# Interface.net
KiCad netlist of a schematic drawn in Altium Designer
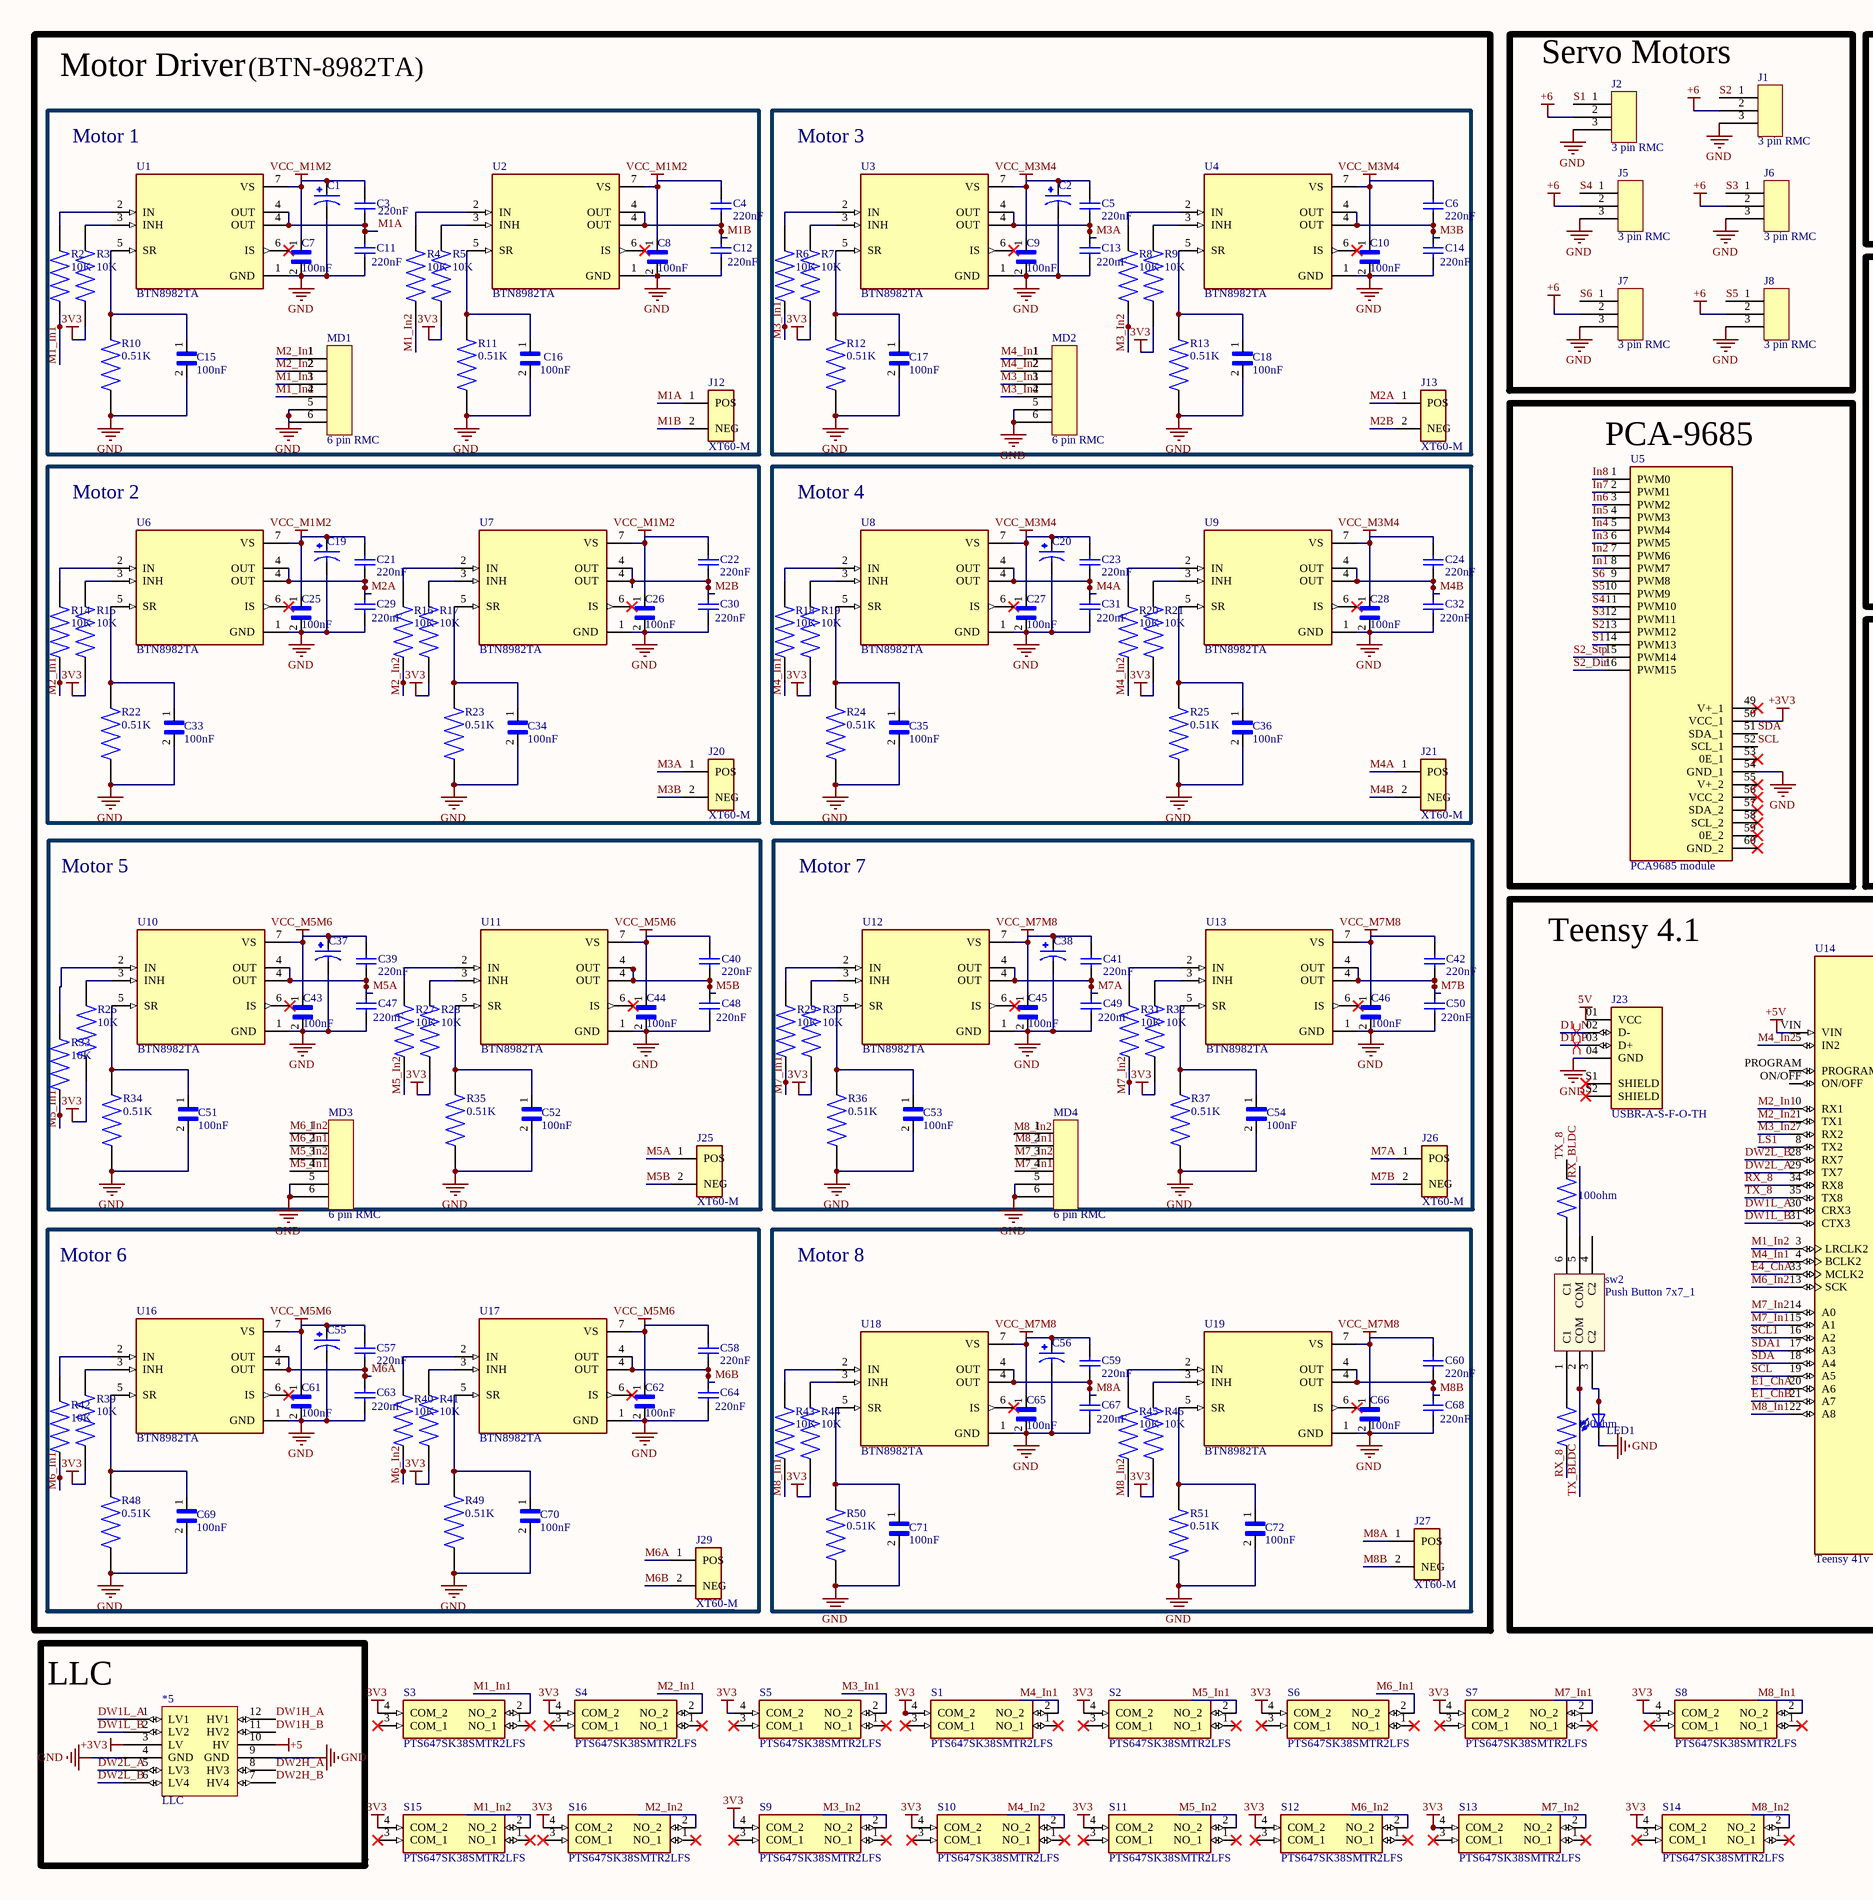
[diagram p0: Interface.SchDoc, left]
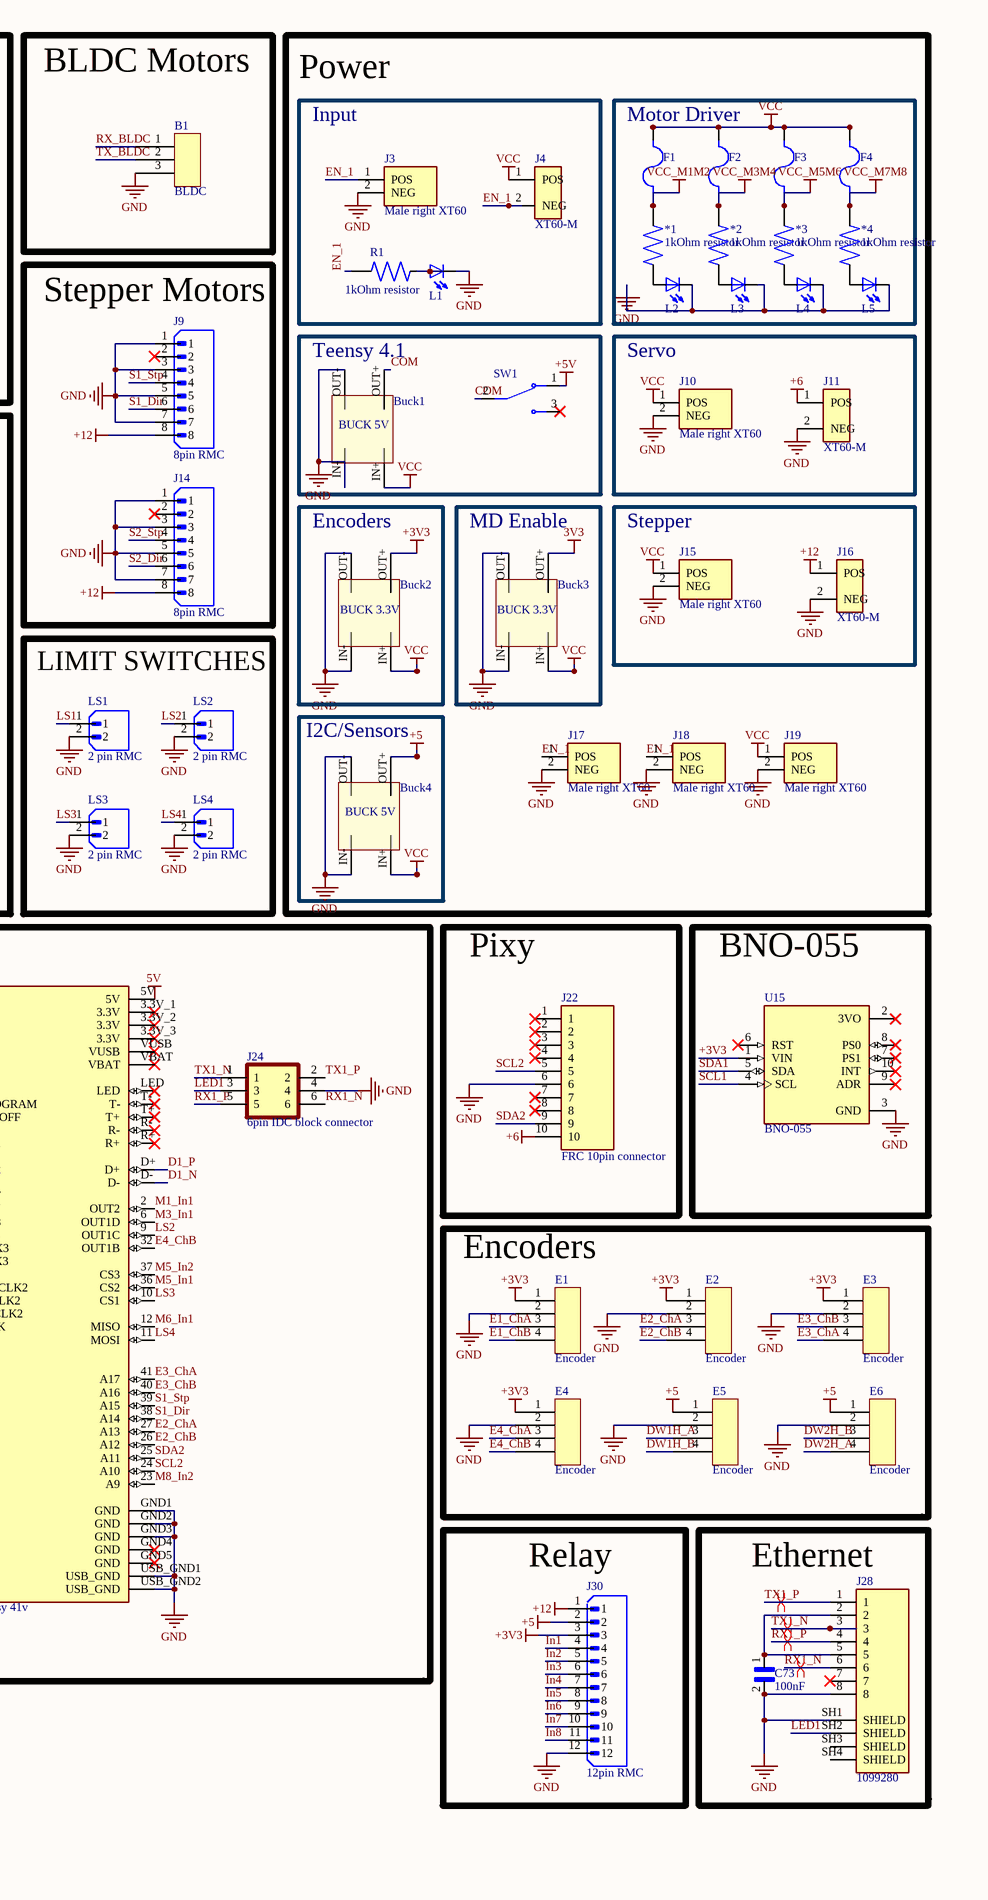
[diagram p1: Interface.SchDoc, right]

(export (version "E")
  (design (tool "Eeschema 10.0.6"))
  (components
    (comp (ref "*1")
      (value "1kOhm resistor")
      (footprint "1kOhm Resistor")
      (libsource (lib "BOT1_2025") (part "1kOhm resistor"))
    )
    (comp (ref "*2")
      (value "1kOhm resistor")
      (footprint "1kOhm Resistor")
      (libsource (lib "BOT1_2025") (part "1kOhm resistor"))
    )
    (comp (ref "*3")
      (value "1kOhm resistor")
      (footprint "1kOhm Resistor")
      (libsource (lib "BOT1_2025") (part "1kOhm resistor"))
    )
    (comp (ref "*4")
      (value "1kOhm resistor")
      (footprint "1kOhm Resistor")
      (libsource (lib "BOT1_2025") (part "1kOhm resistor"))
    )
    (comp (ref "*5") (value "LLC") (footprint "LLC") (libsource (lib "BOT1_2025") (part "LLC")))
    (comp (ref "B1")
      (value "BLDC")
      (footprint "Header JST 1X03")
      (libsource (lib "BOT1_2025") (part "3 pin RMC"))
    )
    (comp (ref "Buck1")
      (value "CN3900 5V")
      (footprint "CN3903 Dubai buck 5V")
      (libsource (lib "BOT1_2025") (part "CN3900 5V"))
    )
    (comp (ref "Buck2")
      (value "CN3900 3.3V")
      (footprint "CN3903 Dubai buck 3.3V")
      (libsource (lib "BOT1_2025") (part "CN3900 3.3V"))
    )
    (comp (ref "Buck3")
      (value "CN3900 3.3V")
      (footprint "CN3903 Dubai buck 3.3V")
      (libsource (lib "BOT1_2025") (part "CN3900 3.3V"))
    )
    (comp (ref "Buck4")
      (value "CN3900 5V")
      (footprint "CN3903 Dubai buck 5V")
      (libsource (lib "BOT1_2025") (part "CN3900 5V"))
    )
    (comp (ref "C1")
      (value "1000uF 25V Capacitor")
      (footprint "1000uF 25V Capacitor")
      (description "CAP ALUM 1000UF 20% 25V RADIAL")
      (fields (field (name "MP") "EEUTA1E102LB") (field (name "MF") "Panasonic"))
      (libsource (lib "BOT1_2025") (part "1000uF 25V Capacitor"))
    )
    (comp (ref "C2")
      (value "1000uF 25V Capacitor")
      (footprint "1000uF 25V Capacitor")
      (description "CAP ALUM 1000UF 20% 25V RADIAL")
      (fields (field (name "MP") "EEUTA1E102LB") (field (name "MF") "Panasonic"))
      (libsource (lib "BOT1_2025") (part "1000uF 25V Capacitor"))
    )
    (comp (ref "C3")
      (value "220nF")
      (footprint "WCAP-CSST_0805_L2W1.25H1.25")
      (fields
        (field (name "MANUFACTURER PART NUMBER") "885382207008")
        (field (name "MANUFACTURER") "Wurth Elektronik")
      )
      (libsource (lib "BOT1_2025") (part "885382207008"))
    )
    (comp (ref "C4")
      (value "220nF")
      (footprint "WCAP-CSST_0805_L2W1.25H1.25")
      (fields
        (field (name "MANUFACTURER PART NUMBER") "885382207008")
        (field (name "MANUFACTURER") "Wurth Elektronik")
      )
      (libsource (lib "BOT1_2025") (part "885382207008"))
    )
    (comp (ref "C5")
      (value "220nF")
      (footprint "WCAP-CSST_0805_L2W1.25H1.25")
      (fields
        (field (name "MANUFACTURER PART NUMBER") "885382207008")
        (field (name "MANUFACTURER") "Wurth Elektronik")
      )
      (libsource (lib "BOT1_2025") (part "885382207008"))
    )
    (comp (ref "C6")
      (value "220nF")
      (footprint "WCAP-CSST_0805_L2W1.25H1.25")
      (fields
        (field (name "MANUFACTURER PART NUMBER") "885382207008")
        (field (name "MANUFACTURER") "Wurth Elektronik")
      )
      (libsource (lib "BOT1_2025") (part "885382207008"))
    )
    (comp (ref "C7")
      (value "100nF")
      (footprint "BOT1_2025:CAPC2012X88N")
      (description "0.1ÂµF Â±10% 50V Ceramic Capacitor X7R 0805 _2012 Metric_")
      (fields (field (name "MF") "KEMET") (field (name "DIGI-KEY_PART_NUMBER") "399-5110-1-ND"))
      (libsource (lib "BOT1_2025") (part "C0805F104K5RACTU"))
    )
    (comp (ref "C8")
      (value "100nF")
      (footprint "BOT1_2025:CAPC2012X88N")
      (description "0.1ÂµF Â±10% 50V Ceramic Capacitor X7R 0805 _2012 Metric_")
      (fields (field (name "MF") "KEMET") (field (name "DIGI-KEY_PART_NUMBER") "399-5110-1-ND"))
      (libsource (lib "BOT1_2025") (part "C0805F104K5RACTU"))
    )
    (comp (ref "C9")
      (value "100nF")
      (footprint "BOT1_2025:CAPC2012X88N")
      (description "0.1ÂµF Â±10% 50V Ceramic Capacitor X7R 0805 _2012 Metric_")
      (fields (field (name "MF") "KEMET") (field (name "DIGI-KEY_PART_NUMBER") "399-5110-1-ND"))
      (libsource (lib "BOT1_2025") (part "C0805F104K5RACTU"))
    )
    (comp (ref "C10")
      (value "100nF")
      (footprint "BOT1_2025:CAPC2012X88N")
      (description "0.1ÂµF Â±10% 50V Ceramic Capacitor X7R 0805 _2012 Metric_")
      (fields (field (name "MF") "KEMET") (field (name "DIGI-KEY_PART_NUMBER") "399-5110-1-ND"))
      (libsource (lib "BOT1_2025") (part "C0805F104K5RACTU"))
    )
    (comp (ref "C11")
      (value "220nF")
      (footprint "WCAP-CSST_0805_L2W1.25H1.25")
      (fields
        (field (name "MANUFACTURER PART NUMBER") "885382207008")
        (field (name "MANUFACTURER") "Wurth Elektronik")
      )
      (libsource (lib "BOT1_2025") (part "885382207008"))
    )
    (comp (ref "C12")
      (value "220nF")
      (footprint "WCAP-CSST_0805_L2W1.25H1.25")
      (fields
        (field (name "MANUFACTURER PART NUMBER") "885382207008")
        (field (name "MANUFACTURER") "Wurth Elektronik")
      )
      (libsource (lib "BOT1_2025") (part "885382207008"))
    )
    (comp (ref "C13")
      (value "220nF")
      (footprint "WCAP-CSST_0805_L2W1.25H1.25")
      (fields
        (field (name "MANUFACTURER PART NUMBER") "885382207008")
        (field (name "MANUFACTURER") "Wurth Elektronik")
      )
      (libsource (lib "BOT1_2025") (part "885382207008"))
    )
    (comp (ref "C14")
      (value "220nF")
      (footprint "WCAP-CSST_0805_L2W1.25H1.25")
      (fields
        (field (name "MANUFACTURER PART NUMBER") "885382207008")
        (field (name "MANUFACTURER") "Wurth Elektronik")
      )
      (libsource (lib "BOT1_2025") (part "885382207008"))
    )
    (comp (ref "C15")
      (value "100nF")
      (footprint "BOT1_2025:CAPC2012X88N")
      (description "0.1ÂµF Â±10% 50V Ceramic Capacitor X7R 0805 _2012 Metric_")
      (fields (field (name "MF") "KEMET") (field (name "DIGI-KEY_PART_NUMBER") "399-5110-1-ND"))
      (libsource (lib "BOT1_2025") (part "C0805F104K5RACTU"))
    )
    (comp (ref "C16")
      (value "100nF")
      (footprint "BOT1_2025:CAPC2012X88N")
      (description "0.1ÂµF Â±10% 50V Ceramic Capacitor X7R 0805 _2012 Metric_")
      (fields (field (name "MF") "KEMET") (field (name "DIGI-KEY_PART_NUMBER") "399-5110-1-ND"))
      (libsource (lib "BOT1_2025") (part "C0805F104K5RACTU"))
    )
    (comp (ref "C17")
      (value "100nF")
      (footprint "BOT1_2025:CAPC2012X88N")
      (description "0.1ÂµF Â±10% 50V Ceramic Capacitor X7R 0805 _2012 Metric_")
      (fields (field (name "MF") "KEMET") (field (name "DIGI-KEY_PART_NUMBER") "399-5110-1-ND"))
      (libsource (lib "BOT1_2025") (part "C0805F104K5RACTU"))
    )
    (comp (ref "C18")
      (value "100nF")
      (footprint "BOT1_2025:CAPC2012X88N")
      (description "0.1ÂµF Â±10% 50V Ceramic Capacitor X7R 0805 _2012 Metric_")
      (fields (field (name "MF") "KEMET") (field (name "DIGI-KEY_PART_NUMBER") "399-5110-1-ND"))
      (libsource (lib "BOT1_2025") (part "C0805F104K5RACTU"))
    )
    (comp (ref "C19")
      (value "1000uF 25V Capacitor")
      (footprint "1000uF 25V Capacitor")
      (description "CAP ALUM 1000UF 20% 25V RADIAL")
      (fields (field (name "MP") "EEUTA1E102LB") (field (name "MF") "Panasonic"))
      (libsource (lib "BOT1_2025") (part "1000uF 25V Capacitor"))
    )
    (comp (ref "C20")
      (value "1000uF 25V Capacitor")
      (footprint "1000uF 25V Capacitor")
      (description "CAP ALUM 1000UF 20% 25V RADIAL")
      (fields (field (name "MP") "EEUTA1E102LB") (field (name "MF") "Panasonic"))
      (libsource (lib "BOT1_2025") (part "1000uF 25V Capacitor"))
    )
    (comp (ref "C21")
      (value "220nF")
      (footprint "WCAP-CSST_0805_L2W1.25H1.25")
      (fields
        (field (name "MANUFACTURER PART NUMBER") "885382207008")
        (field (name "MANUFACTURER") "Wurth Elektronik")
      )
      (libsource (lib "BOT1_2025") (part "885382207008"))
    )
    (comp (ref "C22")
      (value "220nF")
      (footprint "WCAP-CSST_0805_L2W1.25H1.25")
      (fields
        (field (name "MANUFACTURER PART NUMBER") "885382207008")
        (field (name "MANUFACTURER") "Wurth Elektronik")
      )
      (libsource (lib "BOT1_2025") (part "885382207008"))
    )
    (comp (ref "C23")
      (value "220nF")
      (footprint "WCAP-CSST_0805_L2W1.25H1.25")
      (fields
        (field (name "MANUFACTURER PART NUMBER") "885382207008")
        (field (name "MANUFACTURER") "Wurth Elektronik")
      )
      (libsource (lib "BOT1_2025") (part "885382207008"))
    )
    (comp (ref "C24")
      (value "220nF")
      (footprint "WCAP-CSST_0805_L2W1.25H1.25")
      (fields
        (field (name "MANUFACTURER PART NUMBER") "885382207008")
        (field (name "MANUFACTURER") "Wurth Elektronik")
      )
      (libsource (lib "BOT1_2025") (part "885382207008"))
    )
    (comp (ref "C25")
      (value "100nF")
      (footprint "BOT1_2025:CAPC2012X88N")
      (description "0.1ÂµF Â±10% 50V Ceramic Capacitor X7R 0805 _2012 Metric_")
      (fields (field (name "MF") "KEMET") (field (name "DIGI-KEY_PART_NUMBER") "399-5110-1-ND"))
      (libsource (lib "BOT1_2025") (part "C0805F104K5RACTU"))
    )
    (comp (ref "C26")
      (value "100nF")
      (footprint "BOT1_2025:CAPC2012X88N")
      (description "0.1ÂµF Â±10% 50V Ceramic Capacitor X7R 0805 _2012 Metric_")
      (fields (field (name "MF") "KEMET") (field (name "DIGI-KEY_PART_NUMBER") "399-5110-1-ND"))
      (libsource (lib "BOT1_2025") (part "C0805F104K5RACTU"))
    )
    (comp (ref "C27")
      (value "100nF")
      (footprint "BOT1_2025:CAPC2012X88N")
      (description "0.1ÂµF Â±10% 50V Ceramic Capacitor X7R 0805 _2012 Metric_")
      (fields (field (name "MF") "KEMET") (field (name "DIGI-KEY_PART_NUMBER") "399-5110-1-ND"))
      (libsource (lib "BOT1_2025") (part "C0805F104K5RACTU"))
    )
    (comp (ref "C28")
      (value "100nF")
      (footprint "BOT1_2025:CAPC2012X88N")
      (description "0.1ÂµF Â±10% 50V Ceramic Capacitor X7R 0805 _2012 Metric_")
      (fields (field (name "MF") "KEMET") (field (name "DIGI-KEY_PART_NUMBER") "399-5110-1-ND"))
      (libsource (lib "BOT1_2025") (part "C0805F104K5RACTU"))
    )
    (comp (ref "C29")
      (value "220nF")
      (footprint "WCAP-CSST_0805_L2W1.25H1.25")
      (fields
        (field (name "MANUFACTURER PART NUMBER") "885382207008")
        (field (name "MANUFACTURER") "Wurth Elektronik")
      )
      (libsource (lib "BOT1_2025") (part "885382207008"))
    )
    (comp (ref "C30")
      (value "220nF")
      (footprint "WCAP-CSST_0805_L2W1.25H1.25")
      (fields
        (field (name "MANUFACTURER PART NUMBER") "885382207008")
        (field (name "MANUFACTURER") "Wurth Elektronik")
      )
      (libsource (lib "BOT1_2025") (part "885382207008"))
    )
    (comp (ref "C31")
      (value "220nF")
      (footprint "WCAP-CSST_0805_L2W1.25H1.25")
      (fields
        (field (name "MANUFACTURER PART NUMBER") "885382207008")
        (field (name "MANUFACTURER") "Wurth Elektronik")
      )
      (libsource (lib "BOT1_2025") (part "885382207008"))
    )
    (comp (ref "C32")
      (value "220nF")
      (footprint "WCAP-CSST_0805_L2W1.25H1.25")
      (fields
        (field (name "MANUFACTURER PART NUMBER") "885382207008")
        (field (name "MANUFACTURER") "Wurth Elektronik")
      )
      (libsource (lib "BOT1_2025") (part "885382207008"))
    )
    (comp (ref "C33")
      (value "100nF")
      (footprint "BOT1_2025:CAPC2012X88N")
      (description "0.1ÂµF Â±10% 50V Ceramic Capacitor X7R 0805 _2012 Metric_")
      (fields (field (name "MF") "KEMET") (field (name "DIGI-KEY_PART_NUMBER") "399-5110-1-ND"))
      (libsource (lib "BOT1_2025") (part "C0805F104K5RACTU"))
    )
    (comp (ref "C34")
      (value "100nF")
      (footprint "BOT1_2025:CAPC2012X88N")
      (description "0.1ÂµF Â±10% 50V Ceramic Capacitor X7R 0805 _2012 Metric_")
      (fields (field (name "MF") "KEMET") (field (name "DIGI-KEY_PART_NUMBER") "399-5110-1-ND"))
      (libsource (lib "BOT1_2025") (part "C0805F104K5RACTU"))
    )
    (comp (ref "C35")
      (value "100nF")
      (footprint "BOT1_2025:CAPC2012X88N")
      (description "0.1ÂµF Â±10% 50V Ceramic Capacitor X7R 0805 _2012 Metric_")
      (fields (field (name "MF") "KEMET") (field (name "DIGI-KEY_PART_NUMBER") "399-5110-1-ND"))
      (libsource (lib "BOT1_2025") (part "C0805F104K5RACTU"))
    )
    (comp (ref "C36")
      (value "100nF")
      (footprint "BOT1_2025:CAPC2012X88N")
      (description "0.1ÂµF Â±10% 50V Ceramic Capacitor X7R 0805 _2012 Metric_")
      (fields (field (name "MF") "KEMET") (field (name "DIGI-KEY_PART_NUMBER") "399-5110-1-ND"))
      (libsource (lib "BOT1_2025") (part "C0805F104K5RACTU"))
    )
    (comp (ref "C37")
      (value "1000uF 25V Capacitor")
      (footprint "1000uF 25V Capacitor")
      (description "CAP ALUM 1000UF 20% 25V RADIAL")
      (fields (field (name "MP") "EEUTA1E102LB") (field (name "MF") "Panasonic"))
      (libsource (lib "BOT1_2025") (part "1000uF 25V Capacitor"))
    )
    (comp (ref "C38")
      (value "1000uF 25V Capacitor")
      (footprint "1000uF 25V Capacitor")
      (description "CAP ALUM 1000UF 20% 25V RADIAL")
      (fields (field (name "MP") "EEUTA1E102LB") (field (name "MF") "Panasonic"))
      (libsource (lib "BOT1_2025") (part "1000uF 25V Capacitor"))
    )
    (comp (ref "C39")
      (value "220nF")
      (footprint "WCAP-CSST_0805_L2W1.25H1.25")
      (fields
        (field (name "MANUFACTURER PART NUMBER") "885382207008")
        (field (name "MANUFACTURER") "Wurth Elektronik")
      )
      (libsource (lib "BOT1_2025") (part "885382207008"))
    )
    (comp (ref "C40")
      (value "220nF")
      (footprint "WCAP-CSST_0805_L2W1.25H1.25")
      (fields
        (field (name "MANUFACTURER PART NUMBER") "885382207008")
        (field (name "MANUFACTURER") "Wurth Elektronik")
      )
      (libsource (lib "BOT1_2025") (part "885382207008"))
    )
    (comp (ref "C41")
      (value "220nF")
      (footprint "WCAP-CSST_0805_L2W1.25H1.25")
      (fields
        (field (name "MANUFACTURER PART NUMBER") "885382207008")
        (field (name "MANUFACTURER") "Wurth Elektronik")
      )
      (libsource (lib "BOT1_2025") (part "885382207008"))
    )
    (comp (ref "C42")
      (value "220nF")
      (footprint "WCAP-CSST_0805_L2W1.25H1.25")
      (fields
        (field (name "MANUFACTURER PART NUMBER") "885382207008")
        (field (name "MANUFACTURER") "Wurth Elektronik")
      )
      (libsource (lib "BOT1_2025") (part "885382207008"))
    )
    (comp (ref "C43")
      (value "100nF")
      (footprint "BOT1_2025:CAPC2012X88N")
      (description "0.1ÂµF Â±10% 50V Ceramic Capacitor X7R 0805 _2012 Metric_")
      (fields (field (name "MF") "KEMET") (field (name "DIGI-KEY_PART_NUMBER") "399-5110-1-ND"))
      (libsource (lib "BOT1_2025") (part "C0805F104K5RACTU"))
    )
    (comp (ref "C44")
      (value "100nF")
      (footprint "BOT1_2025:CAPC2012X88N")
      (description "0.1ÂµF Â±10% 50V Ceramic Capacitor X7R 0805 _2012 Metric_")
      (fields (field (name "MF") "KEMET") (field (name "DIGI-KEY_PART_NUMBER") "399-5110-1-ND"))
      (libsource (lib "BOT1_2025") (part "C0805F104K5RACTU"))
    )
    (comp (ref "C45")
      (value "100nF")
      (footprint "BOT1_2025:CAPC2012X88N")
      (description "0.1ÂµF Â±10% 50V Ceramic Capacitor X7R 0805 _2012 Metric_")
      (fields (field (name "MF") "KEMET") (field (name "DIGI-KEY_PART_NUMBER") "399-5110-1-ND"))
      (libsource (lib "BOT1_2025") (part "C0805F104K5RACTU"))
    )
    (comp (ref "C46")
      (value "100nF")
      (footprint "BOT1_2025:CAPC2012X88N")
      (description "0.1ÂµF Â±10% 50V Ceramic Capacitor X7R 0805 _2012 Metric_")
      (fields (field (name "MF") "KEMET") (field (name "DIGI-KEY_PART_NUMBER") "399-5110-1-ND"))
      (libsource (lib "BOT1_2025") (part "C0805F104K5RACTU"))
    )
    (comp (ref "C47")
      (value "220nF")
      (footprint "WCAP-CSST_0805_L2W1.25H1.25")
      (fields
        (field (name "MANUFACTURER PART NUMBER") "885382207008")
        (field (name "MANUFACTURER") "Wurth Elektronik")
      )
      (libsource (lib "BOT1_2025") (part "885382207008"))
    )
    (comp (ref "C48")
      (value "220nF")
      (footprint "WCAP-CSST_0805_L2W1.25H1.25")
      (fields
        (field (name "MANUFACTURER PART NUMBER") "885382207008")
        (field (name "MANUFACTURER") "Wurth Elektronik")
      )
      (libsource (lib "BOT1_2025") (part "885382207008"))
    )
    (comp (ref "C49")
      (value "220nF")
      (footprint "WCAP-CSST_0805_L2W1.25H1.25")
      (fields
        (field (name "MANUFACTURER PART NUMBER") "885382207008")
        (field (name "MANUFACTURER") "Wurth Elektronik")
      )
      (libsource (lib "BOT1_2025") (part "885382207008"))
    )
    (comp (ref "C50")
      (value "220nF")
      (footprint "WCAP-CSST_0805_L2W1.25H1.25")
      (fields
        (field (name "MANUFACTURER PART NUMBER") "885382207008")
        (field (name "MANUFACTURER") "Wurth Elektronik")
      )
      (libsource (lib "BOT1_2025") (part "885382207008"))
    )
    (comp (ref "C51")
      (value "100nF")
      (footprint "BOT1_2025:CAPC2012X88N")
      (description "0.1ÂµF Â±10% 50V Ceramic Capacitor X7R 0805 _2012 Metric_")
      (fields (field (name "MF") "KEMET") (field (name "DIGI-KEY_PART_NUMBER") "399-5110-1-ND"))
      (libsource (lib "BOT1_2025") (part "C0805F104K5RACTU"))
    )
    (comp (ref "C52")
      (value "100nF")
      (footprint "BOT1_2025:CAPC2012X88N")
      (description "0.1ÂµF Â±10% 50V Ceramic Capacitor X7R 0805 _2012 Metric_")
      (fields (field (name "MF") "KEMET") (field (name "DIGI-KEY_PART_NUMBER") "399-5110-1-ND"))
      (libsource (lib "BOT1_2025") (part "C0805F104K5RACTU"))
    )
    (comp (ref "C53")
      (value "100nF")
      (footprint "BOT1_2025:CAPC2012X88N")
      (description "0.1ÂµF Â±10% 50V Ceramic Capacitor X7R 0805 _2012 Metric_")
      (fields (field (name "MF") "KEMET") (field (name "DIGI-KEY_PART_NUMBER") "399-5110-1-ND"))
      (libsource (lib "BOT1_2025") (part "C0805F104K5RACTU"))
    )
    (comp (ref "C54")
      (value "100nF")
      (footprint "BOT1_2025:CAPC2012X88N")
      (description "0.1ÂµF Â±10% 50V Ceramic Capacitor X7R 0805 _2012 Metric_")
      (fields (field (name "MF") "KEMET") (field (name "DIGI-KEY_PART_NUMBER") "399-5110-1-ND"))
      (libsource (lib "BOT1_2025") (part "C0805F104K5RACTU"))
    )
    (comp (ref "C55")
      (value "1000uF 25V Capacitor")
      (footprint "1000uF 25V Capacitor")
      (description "CAP ALUM 1000UF 20% 25V RADIAL")
      (fields (field (name "MP") "EEUTA1E102LB") (field (name "MF") "Panasonic"))
      (libsource (lib "BOT1_2025") (part "1000uF 25V Capacitor"))
    )
    (comp (ref "C56")
      (value "1000uF 25V Capacitor")
      (footprint "1000uF 25V Capacitor")
      (description "CAP ALUM 1000UF 20% 25V RADIAL")
      (fields (field (name "MP") "EEUTA1E102LB") (field (name "MF") "Panasonic"))
      (libsource (lib "BOT1_2025") (part "1000uF 25V Capacitor"))
    )
    (comp (ref "C57")
      (value "220nF")
      (footprint "WCAP-CSST_0805_L2W1.25H1.25")
      (fields
        (field (name "MANUFACTURER PART NUMBER") "885382207008")
        (field (name "MANUFACTURER") "Wurth Elektronik")
      )
      (libsource (lib "BOT1_2025") (part "885382207008"))
    )
    (comp (ref "C58")
      (value "220nF")
      (footprint "WCAP-CSST_0805_L2W1.25H1.25")
      (fields
        (field (name "MANUFACTURER PART NUMBER") "885382207008")
        (field (name "MANUFACTURER") "Wurth Elektronik")
      )
      (libsource (lib "BOT1_2025") (part "885382207008"))
    )
    (comp (ref "C59")
      (value "220nF")
      (footprint "WCAP-CSST_0805_L2W1.25H1.25")
      (fields
        (field (name "MANUFACTURER PART NUMBER") "885382207008")
        (field (name "MANUFACTURER") "Wurth Elektronik")
      )
      (libsource (lib "BOT1_2025") (part "885382207008"))
    )
    (comp (ref "C60")
      (value "220nF")
      (footprint "WCAP-CSST_0805_L2W1.25H1.25")
      (fields
        (field (name "MANUFACTURER PART NUMBER") "885382207008")
        (field (name "MANUFACTURER") "Wurth Elektronik")
      )
      (libsource (lib "BOT1_2025") (part "885382207008"))
    )
    (comp (ref "C61")
      (value "100nF")
      (footprint "BOT1_2025:CAPC2012X88N")
      (description "0.1ÂµF Â±10% 50V Ceramic Capacitor X7R 0805 _2012 Metric_")
      (fields (field (name "MF") "KEMET") (field (name "DIGI-KEY_PART_NUMBER") "399-5110-1-ND"))
      (libsource (lib "BOT1_2025") (part "C0805F104K5RACTU"))
    )
    (comp (ref "C62")
      (value "100nF")
      (footprint "BOT1_2025:CAPC2012X88N")
      (description "0.1ÂµF Â±10% 50V Ceramic Capacitor X7R 0805 _2012 Metric_")
      (fields (field (name "MF") "KEMET") (field (name "DIGI-KEY_PART_NUMBER") "399-5110-1-ND"))
      (libsource (lib "BOT1_2025") (part "C0805F104K5RACTU"))
    )
    (comp (ref "C63")
      (value "220nF")
      (footprint "WCAP-CSST_0805_L2W1.25H1.25")
      (fields
        (field (name "MANUFACTURER PART NUMBER") "885382207008")
        (field (name "MANUFACTURER") "Wurth Elektronik")
      )
      (libsource (lib "BOT1_2025") (part "885382207008"))
    )
    (comp (ref "C64")
      (value "220nF")
      (footprint "WCAP-CSST_0805_L2W1.25H1.25")
      (fields
        (field (name "MANUFACTURER PART NUMBER") "885382207008")
        (field (name "MANUFACTURER") "Wurth Elektronik")
      )
      (libsource (lib "BOT1_2025") (part "885382207008"))
    )
    (comp (ref "C65")
      (value "100nF")
      (footprint "BOT1_2025:CAPC2012X88N")
      (description "0.1ÂµF Â±10% 50V Ceramic Capacitor X7R 0805 _2012 Metric_")
      (fields (field (name "MF") "KEMET") (field (name "DIGI-KEY_PART_NUMBER") "399-5110-1-ND"))
      (libsource (lib "BOT1_2025") (part "C0805F104K5RACTU"))
    )
    (comp (ref "C66")
      (value "100nF")
      (footprint "BOT1_2025:CAPC2012X88N")
      (description "0.1ÂµF Â±10% 50V Ceramic Capacitor X7R 0805 _2012 Metric_")
      (fields (field (name "MF") "KEMET") (field (name "DIGI-KEY_PART_NUMBER") "399-5110-1-ND"))
      (libsource (lib "BOT1_2025") (part "C0805F104K5RACTU"))
    )
    (comp (ref "C67")
      (value "220nF")
      (footprint "WCAP-CSST_0805_L2W1.25H1.25")
      (fields
        (field (name "MANUFACTURER PART NUMBER") "885382207008")
        (field (name "MANUFACTURER") "Wurth Elektronik")
      )
      (libsource (lib "BOT1_2025") (part "885382207008"))
    )
    (comp (ref "C68")
      (value "220nF")
      (footprint "WCAP-CSST_0805_L2W1.25H1.25")
      (fields
        (field (name "MANUFACTURER PART NUMBER") "885382207008")
        (field (name "MANUFACTURER") "Wurth Elektronik")
      )
      (libsource (lib "BOT1_2025") (part "885382207008"))
    )
    (comp (ref "C69")
      (value "100nF")
      (footprint "BOT1_2025:CAPC2012X88N")
      (description "0.1ÂµF Â±10% 50V Ceramic Capacitor X7R 0805 _2012 Metric_")
      (fields (field (name "MF") "KEMET") (field (name "DIGI-KEY_PART_NUMBER") "399-5110-1-ND"))
      (libsource (lib "BOT1_2025") (part "C0805F104K5RACTU"))
    )
    (comp (ref "C70")
      (value "100nF")
      (footprint "BOT1_2025:CAPC2012X88N")
      (description "0.1ÂµF Â±10% 50V Ceramic Capacitor X7R 0805 _2012 Metric_")
      (fields (field (name "MF") "KEMET") (field (name "DIGI-KEY_PART_NUMBER") "399-5110-1-ND"))
      (libsource (lib "BOT1_2025") (part "C0805F104K5RACTU"))
    )
    (comp (ref "C71")
      (value "100nF")
      (footprint "BOT1_2025:CAPC2012X88N")
      (description "0.1ÂµF Â±10% 50V Ceramic Capacitor X7R 0805 _2012 Metric_")
      (fields (field (name "MF") "KEMET") (field (name "DIGI-KEY_PART_NUMBER") "399-5110-1-ND"))
      (libsource (lib "BOT1_2025") (part "C0805F104K5RACTU"))
    )
    (comp (ref "C72")
      (value "100nF")
      (footprint "BOT1_2025:CAPC2012X88N")
      (description "0.1ÂµF Â±10% 50V Ceramic Capacitor X7R 0805 _2012 Metric_")
      (fields (field (name "MF") "KEMET") (field (name "DIGI-KEY_PART_NUMBER") "399-5110-1-ND"))
      (libsource (lib "BOT1_2025") (part "C0805F104K5RACTU"))
    )
    (comp (ref "C73")
      (value "100nF")
      (footprint "BOT1_2025:CAPC2012X88N")
      (description "0.1ÂµF Â±10% 50V Ceramic Capacitor X7R 0805 _2012 Metric_")
      (fields (field (name "MF") "KEMET") (field (name "DIGI-KEY_PART_NUMBER") "399-5110-1-ND"))
      (libsource (lib "BOT1_2025") (part "C0805F104K5RACTU"))
    )
    (comp (ref "E1")
      (value "Encoder")
      (footprint "Header JST 1X04")
      (libsource (lib "BOT1_2025") (part "4 pin RMC"))
    )
    (comp (ref "E2")
      (value "Encoder")
      (footprint "Header JST 1X04")
      (libsource (lib "BOT1_2025") (part "4 pin RMC"))
    )
    (comp (ref "E3")
      (value "Encoder")
      (footprint "Header JST 1X04")
      (libsource (lib "BOT1_2025") (part "4 pin RMC"))
    )
    (comp (ref "E4")
      (value "Encoder")
      (footprint "Header JST 1X04")
      (libsource (lib "BOT1_2025") (part "4 pin RMC"))
    )
    (comp (ref "E5")
      (value "Encoder")
      (footprint "Header JST 1X04")
      (libsource (lib "BOT1_2025") (part "4 pin RMC"))
    )
    (comp (ref "E6")
      (value "Encoder")
      (footprint "Header JST 1X04")
      (libsource (lib "BOT1_2025") (part "4 pin RMC"))
    )
    (comp (ref "F1")
      (value "Blade Fuse Holder")
      (footprint "Blade fuse holder")
      (libsource (lib "BOT1_2025") (part "Blade Fuse Holder"))
    )
    (comp (ref "F2")
      (value "Blade Fuse Holder")
      (footprint "Blade fuse holder")
      (libsource (lib "BOT1_2025") (part "Blade Fuse Holder"))
    )
    (comp (ref "F3")
      (value "Blade Fuse Holder")
      (footprint "Blade fuse holder")
      (libsource (lib "BOT1_2025") (part "Blade Fuse Holder"))
    )
    (comp (ref "F4")
      (value "Blade Fuse Holder")
      (footprint "Blade fuse holder")
      (libsource (lib "BOT1_2025") (part "Blade Fuse Holder"))
    )
    (comp (ref "J1")
      (value "3 pin RMC")
      (footprint "Header JST 1X03")
      (libsource (lib "BOT1_2025") (part "3 pin RMC"))
    )
    (comp (ref "J2")
      (value "3 pin RMC")
      (footprint "Header JST 1X03")
      (libsource (lib "BOT1_2025") (part "3 pin RMC"))
    )
    (comp (ref "J3")
      (value "Male right XT60")
      (footprint "XT60M Right")
      (libsource (lib "BOT1_2025") (part "XT60M Right"))
    )
    (comp (ref "J4")
      (value "XT60-M")
      (footprint "XT-60M")
      (description "Plug; DC supply; XT60; male; PIN: 2; for cable; soldered; 30A; 500V")
      (fields (field (name "MF") "AMASS"))
      (libsource (lib "BOT1_2025") (part "XT60-M_1"))
    )
    (comp (ref "J5")
      (value "3 pin RMC")
      (footprint "Header JST 1X03")
      (libsource (lib "BOT1_2025") (part "3 pin RMC"))
    )
    (comp (ref "J6")
      (value "3 pin RMC")
      (footprint "Header JST 1X03")
      (libsource (lib "BOT1_2025") (part "3 pin RMC"))
    )
    (comp (ref "J7")
      (value "3 pin RMC")
      (footprint "Header JST 1X03")
      (libsource (lib "BOT1_2025") (part "3 pin RMC"))
    )
    (comp (ref "J8")
      (value "3 pin RMC")
      (footprint "Header JST 1X03")
      (libsource (lib "BOT1_2025") (part "3 pin RMC"))
    )
    (comp (ref "J9")
      (value "8pin RMC")
      (footprint "8pin RMC")
      (description "8 pin RMC")
      (libsource (lib "BOT1_2025") (part "8pin RMC"))
    )
    (comp (ref "J10")
      (value "Male right XT60")
      (footprint "XT60M Right")
      (libsource (lib "BOT1_2025") (part "XT60M Right"))
    )
    (comp (ref "J11")
      (value "XT60-M")
      (footprint "XT60-M")
      (description "Plug; DC supply; XT60; male; PIN: 2; for cable; soldered; 30A; 500V")
      (fields (field (name "MF") "AMASS"))
      (libsource (lib "BOT1_2025") (part "XT60-M"))
    )
    (comp (ref "J12")
      (value "XT60-M")
      (footprint "XT60-M")
      (description "Plug; DC supply; XT60; male; PIN: 2; for cable; soldered; 30A; 500V")
      (fields (field (name "MF") "AMASS"))
      (libsource (lib "BOT1_2025") (part "XT60-M"))
    )
    (comp (ref "J13")
      (value "XT60-M")
      (footprint "XT60-M")
      (description "Plug; DC supply; XT60; male; PIN: 2; for cable; soldered; 30A; 500V")
      (fields (field (name "MF") "AMASS"))
      (libsource (lib "BOT1_2025") (part "XT60-M"))
    )
    (comp (ref "J14")
      (value "8pin RMC")
      (footprint "8pin RMC")
      (description "8 pin RMC")
      (libsource (lib "BOT1_2025") (part "8pin RMC"))
    )
    (comp (ref "J15")
      (value "Male right XT60")
      (footprint "XT60M Right")
      (libsource (lib "BOT1_2025") (part "XT60M Right"))
    )
    (comp (ref "J16")
      (value "XT60-M")
      (footprint "XT60-M")
      (description "Plug; DC supply; XT60; male; PIN: 2; for cable; soldered; 30A; 500V")
      (fields (field (name "MF") "AMASS"))
      (libsource (lib "BOT1_2025") (part "XT60-M"))
    )
    (comp (ref "J17")
      (value "Male right XT60")
      (footprint "XT60M Right")
      (libsource (lib "BOT1_2025") (part "XT60M Right"))
    )
    (comp (ref "J18")
      (value "Male right XT60")
      (footprint "XT60M Right")
      (libsource (lib "BOT1_2025") (part "XT60M Right"))
    )
    (comp (ref "J19")
      (value "Male right XT60")
      (footprint "XT60M Right")
      (libsource (lib "BOT1_2025") (part "XT60M Right"))
    )
    (comp (ref "J20")
      (value "XT60-M")
      (footprint "XT60-M")
      (description "Plug; DC supply; XT60; male; PIN: 2; for cable; soldered; 30A; 500V")
      (fields (field (name "MF") "AMASS"))
      (libsource (lib "BOT1_2025") (part "XT60-M"))
    )
    (comp (ref "J21")
      (value "XT60-M")
      (footprint "XT60-M")
      (description "Plug; DC supply; XT60; male; PIN: 2; for cable; soldered; 30A; 500V")
      (fields (field (name "MF") "AMASS"))
      (libsource (lib "BOT1_2025") (part "XT60-M"))
    )
    (comp (ref "J22")
      (value "FRC 10pin connector")
      (footprint "FRC 10pin Block connector")
      (description "Conn Shrouded Header HDR 10 POS 2.54mm Solder ST Thru-Hole Tray")
      (fields (field (name "MP") "1761681-3") (field (name "MF") "TE Connectivity"))
      (libsource (lib "BOT1_2025") (part "FRC 10pin connector"))
    )
    (comp (ref "J23")
      (value "USBR-A-S-F-O-TH")
      (footprint "SAMTEC_USBR-A-S-F-O-TH")
      (description "USB-A _USB TYPE-A_ USB 2.0 Receptacle Connector 4 Position Through Hole, Right Angle")
      (fields (field (name "MF") "Samtec"))
      (libsource (lib "BOT1_2025") (part "USBR-A-S-F-O-TH"))
    )
    (comp (ref "J24")
      (value "6pin IDC block connector")
      (footprint "6pin IDC block connector")
      (description "AMP-LATCH 6 Position 2.54 mm Dual Row Through-Hole Straight Pin Header")
      (fields (field (name "MP") "2-1761603-1") (field (name "MF") "TE Connectivity"))
      (libsource (lib "BOT1_2025") (part "6pin IDC block connector"))
    )
    (comp (ref "J25")
      (value "XT60-M")
      (footprint "XT60-M")
      (description "Plug; DC supply; XT60; male; PIN: 2; for cable; soldered; 30A; 500V")
      (fields (field (name "MF") "AMASS"))
      (libsource (lib "BOT1_2025") (part "XT60-M"))
    )
    (comp (ref "J26")
      (value "XT60-M")
      (footprint "XT60-M")
      (description "Plug; DC supply; XT60; male; PIN: 2; for cable; soldered; 30A; 500V")
      (fields (field (name "MF") "AMASS"))
      (libsource (lib "BOT1_2025") (part "XT60-M"))
    )
    (comp (ref "J27")
      (value "XT60-M")
      (footprint "XT60-M")
      (description "Plug; DC supply; XT60; male; PIN: 2; for cable; soldered; 30A; 500V")
      (fields (field (name "MF") "AMASS"))
      (libsource (lib "BOT1_2025") (part "XT60-M"))
    )
    (comp (ref "J28")
      (value "1099280")
      (footprint "PHOENIX_1099280")
      (description "RJ45 Ethernet port")
      (libsource (lib "BOT1_2025") (part "1099280"))
    )
    (comp (ref "J29")
      (value "XT60-M")
      (footprint "XT60-M")
      (description "Plug; DC supply; XT60; male; PIN: 2; for cable; soldered; 30A; 500V")
      (fields (field (name "MF") "AMASS"))
      (libsource (lib "BOT1_2025") (part "XT60-M"))
    )
    (comp (ref "J30")
      (value "12pin RMC")
      (footprint "Header JST 1X12")
      (description "12 pin RMC")
      (libsource (lib "BOT1_2025") (part "12pin RMC"))
    )
    (comp (ref "L1") (value "LED 3mm") (footprint "LED 3mm") (libsource (lib "R1") (part "LED 3mm")))
    (comp (ref "L2") (value "LED 3mm") (footprint "LED 3mm") (libsource (lib "R1") (part "LED 3mm")))
    (comp (ref "L3") (value "LED 3mm") (footprint "LED 3mm") (libsource (lib "R1") (part "LED 3mm")))
    (comp (ref "L4") (value "LED 3mm") (footprint "LED 3mm") (libsource (lib "R1") (part "LED 3mm")))
    (comp (ref "L5") (value "LED 3mm") (footprint "LED 3mm") (libsource (lib "R1") (part "LED 3mm")))
    (comp (ref "LED1") (value "LED 3mm") (footprint "LED 3mm") (libsource (lib "BOT1_2025") (part "LED 3mm")))
    (comp (ref "LS1")
      (value "2 pin RMC")
      (footprint "JST 2 PIN")
      (description "Connector Header Through Hole 2 position 0.098 (2.50mm) JST")
      (fields (field (name "MF") "JST Sales America Inc.") (field (name "MP") "B2B-XH-A(LF)(SN)"))
      (libsource (lib "BOT1_2025") (part "2 pin RMC"))
    )
    (comp (ref "LS2")
      (value "2 pin RMC")
      (footprint "JST 2 PIN")
      (description "Connector Header Through Hole 2 position 0.098 (2.50mm) JST")
      (fields (field (name "MF") "JST Sales America Inc.") (field (name "MP") "B2B-XH-A(LF)(SN)"))
      (libsource (lib "BOT1_2025") (part "2 pin RMC"))
    )
    (comp (ref "LS3")
      (value "2 pin RMC")
      (footprint "JST 2 PIN")
      (description "Connector Header Through Hole 2 position 0.098 (2.50mm) JST")
      (fields (field (name "MF") "JST Sales America Inc.") (field (name "MP") "B2B-XH-A(LF)(SN)"))
      (libsource (lib "BOT1_2025") (part "2 pin RMC"))
    )
    (comp (ref "LS4")
      (value "2 pin RMC")
      (footprint "JST 2 PIN")
      (description "Connector Header Through Hole 2 position 0.098 (2.50mm) JST")
      (fields (field (name "MF") "JST Sales America Inc.") (field (name "MP") "B2B-XH-A(LF)(SN)"))
      (libsource (lib "BOT1_2025") (part "2 pin RMC"))
    )
    (comp (ref "MD1")
      (value "6 pin RMC")
      (footprint "HEADER JST 1X06")
      (libsource (lib "BOT1_2025") (part "6 pin RMC"))
    )
    (comp (ref "MD2")
      (value "6 pin RMC")
      (footprint "HEADER JST 1X06")
      (libsource (lib "BOT1_2025") (part "6 pin RMC"))
    )
    (comp (ref "MD3")
      (value "6 pin RMC")
      (footprint "HEADER JST 1X06")
      (libsource (lib "BOT1_2025") (part "6 pin RMC"))
    )
    (comp (ref "MD4")
      (value "6 pin RMC")
      (footprint "HEADER JST 1X06")
      (libsource (lib "BOT1_2025") (part "6 pin RMC"))
    )
    (comp (ref "R1")
      (value "1kOhm resistor")
      (footprint "1kOhm Resistor")
      (libsource (lib "BOT1_2025") (part "1kOhm resistor"))
    )
    (comp (ref "R2")
      (value "10K")
      (footprint "RESC2012X65N")
      (description "10k ohm 0805 smd resistor")
      (fields
        (field (name "MF") "{'manufacturer': u'Stackpole Electronics Inc'}")
        (field (name "MP") "RMCF0805FT10K0")
      )
      (libsource (lib "BOT1_2025") (part "RMCF0805FT10K0"))
    )
    (comp (ref "R3")
      (value "10K")
      (footprint "RESC2012X65N")
      (description "10k ohm 0805 smd resistor")
      (fields
        (field (name "MF") "{'manufacturer': u'Stackpole Electronics Inc'}")
        (field (name "MP") "RMCF0805FT10K0")
      )
      (libsource (lib "BOT1_2025") (part "RMCF0805FT10K0"))
    )
    (comp (ref "R4")
      (value "10K")
      (footprint "RESC2012X65N")
      (description "10k ohm 0805 smd resistor")
      (fields
        (field (name "MF") "{'manufacturer': u'Stackpole Electronics Inc'}")
        (field (name "MP") "RMCF0805FT10K0")
      )
      (libsource (lib "BOT1_2025") (part "RMCF0805FT10K0"))
    )
    (comp (ref "R5")
      (value "10K")
      (footprint "RESC2012X65N")
      (description "10k ohm 0805 smd resistor")
      (fields
        (field (name "MF") "{'manufacturer': u'Stackpole Electronics Inc'}")
        (field (name "MP") "RMCF0805FT10K0")
      )
      (libsource (lib "BOT1_2025") (part "RMCF0805FT10K0"))
    )
    (comp (ref "R6")
      (value "10K")
      (footprint "RESC2012X65N")
      (description "10k ohm 0805 smd resistor")
      (fields
        (field (name "MF") "{'manufacturer': u'Stackpole Electronics Inc'}")
        (field (name "MP") "RMCF0805FT10K0")
      )
      (libsource (lib "BOT1_2025") (part "RMCF0805FT10K0"))
    )
    (comp (ref "R7")
      (value "10K")
      (footprint "RESC2012X65N")
      (description "10k ohm 0805 smd resistor")
      (fields
        (field (name "MF") "{'manufacturer': u'Stackpole Electronics Inc'}")
        (field (name "MP") "RMCF0805FT10K0")
      )
      (libsource (lib "BOT1_2025") (part "RMCF0805FT10K0"))
    )
    (comp (ref "R8")
      (value "10K")
      (footprint "RESC2012X65N")
      (description "10k ohm 0805 smd resistor")
      (fields
        (field (name "MF") "{'manufacturer': u'Stackpole Electronics Inc'}")
        (field (name "MP") "RMCF0805FT10K0")
      )
      (libsource (lib "BOT1_2025") (part "RMCF0805FT10K0"))
    )
    (comp (ref "R9")
      (value "10K")
      (footprint "RESC2012X65N")
      (description "10k ohm 0805 smd resistor")
      (fields
        (field (name "MF") "{'manufacturer': u'Stackpole Electronics Inc'}")
        (field (name "MP") "RMCF0805FT10K0")
      )
      (libsource (lib "BOT1_2025") (part "RMCF0805FT10K0"))
    )
    (comp (ref "R10")
      (value "0.51K")
      (footprint "BOT1_2025:RES_ERJHP6F5112V")
      (description "0805 0.51k ohm")
      (fields (field (name "MP") "ERJHP6F5112V"))
      (libsource (lib "BOT1_2025") (part "ERJHP6F5112V"))
    )
    (comp (ref "R11")
      (value "0.51K")
      (footprint "BOT1_2025:RES_ERJHP6F5112V")
      (description "0805 0.51k ohm")
      (fields (field (name "MP") "ERJHP6F5112V"))
      (libsource (lib "BOT1_2025") (part "ERJHP6F5112V"))
    )
    (comp (ref "R12")
      (value "0.51K")
      (footprint "BOT1_2025:RES_ERJHP6F5112V")
      (description "0805 0.51k ohm")
      (fields (field (name "MP") "ERJHP6F5112V"))
      (libsource (lib "BOT1_2025") (part "ERJHP6F5112V"))
    )
    (comp (ref "R13")
      (value "0.51K")
      (footprint "BOT1_2025:RES_ERJHP6F5112V")
      (description "0805 0.51k ohm")
      (fields (field (name "MP") "ERJHP6F5112V"))
      (libsource (lib "BOT1_2025") (part "ERJHP6F5112V"))
    )
    (comp (ref "R14")
      (value "10K")
      (footprint "RESC2012X65N")
      (description "10k ohm 0805 smd resistor")
      (fields
        (field (name "MF") "{'manufacturer': u'Stackpole Electronics Inc'}")
        (field (name "MP") "RMCF0805FT10K0")
      )
      (libsource (lib "BOT1_2025") (part "RMCF0805FT10K0"))
    )
    (comp (ref "R15")
      (value "10K")
      (footprint "RESC2012X65N")
      (description "10k ohm 0805 smd resistor")
      (fields
        (field (name "MF") "{'manufacturer': u'Stackpole Electronics Inc'}")
        (field (name "MP") "RMCF0805FT10K0")
      )
      (libsource (lib "BOT1_2025") (part "RMCF0805FT10K0"))
    )
    (comp (ref "R16")
      (value "10K")
      (footprint "RESC2012X65N")
      (description "10k ohm 0805 smd resistor")
      (fields
        (field (name "MF") "{'manufacturer': u'Stackpole Electronics Inc'}")
        (field (name "MP") "RMCF0805FT10K0")
      )
      (libsource (lib "BOT1_2025") (part "RMCF0805FT10K0"))
    )
    (comp (ref "R17")
      (value "10K")
      (footprint "RESC2012X65N")
      (description "10k ohm 0805 smd resistor")
      (fields
        (field (name "MF") "{'manufacturer': u'Stackpole Electronics Inc'}")
        (field (name "MP") "RMCF0805FT10K0")
      )
      (libsource (lib "BOT1_2025") (part "RMCF0805FT10K0"))
    )
    (comp (ref "R18")
      (value "10K")
      (footprint "RESC2012X65N")
      (description "10k ohm 0805 smd resistor")
      (fields
        (field (name "MF") "{'manufacturer': u'Stackpole Electronics Inc'}")
        (field (name "MP") "RMCF0805FT10K0")
      )
      (libsource (lib "BOT1_2025") (part "RMCF0805FT10K0"))
    )
    (comp (ref "R19")
      (value "10K")
      (footprint "RESC2012X65N")
      (description "10k ohm 0805 smd resistor")
      (fields
        (field (name "MF") "{'manufacturer': u'Stackpole Electronics Inc'}")
        (field (name "MP") "RMCF0805FT10K0")
      )
      (libsource (lib "BOT1_2025") (part "RMCF0805FT10K0"))
    )
    (comp (ref "R20")
      (value "10K")
      (footprint "RESC2012X65N")
      (description "10k ohm 0805 smd resistor")
      (fields
        (field (name "MF") "{'manufacturer': u'Stackpole Electronics Inc'}")
        (field (name "MP") "RMCF0805FT10K0")
      )
      (libsource (lib "BOT1_2025") (part "RMCF0805FT10K0"))
    )
    (comp (ref "R21")
      (value "10K")
      (footprint "RESC2012X65N")
      (description "10k ohm 0805 smd resistor")
      (fields
        (field (name "MF") "{'manufacturer': u'Stackpole Electronics Inc'}")
        (field (name "MP") "RMCF0805FT10K0")
      )
      (libsource (lib "BOT1_2025") (part "RMCF0805FT10K0"))
    )
    (comp (ref "R22")
      (value "0.51K")
      (footprint "BOT1_2025:RES_ERJHP6F5112V")
      (description "0805 0.51k ohm")
      (fields (field (name "MP") "ERJHP6F5112V"))
      (libsource (lib "BOT1_2025") (part "ERJHP6F5112V"))
    )
    (comp (ref "R23")
      (value "0.51K")
      (footprint "BOT1_2025:RES_ERJHP6F5112V")
      (description "0805 0.51k ohm")
      (fields (field (name "MP") "ERJHP6F5112V"))
      (libsource (lib "BOT1_2025") (part "ERJHP6F5112V"))
    )
    (comp (ref "R24")
      (value "0.51K")
      (footprint "BOT1_2025:RES_ERJHP6F5112V")
      (description "0805 0.51k ohm")
      (fields (field (name "MP") "ERJHP6F5112V"))
      (libsource (lib "BOT1_2025") (part "ERJHP6F5112V"))
    )
    (comp (ref "R25")
      (value "0.51K")
      (footprint "BOT1_2025:RES_ERJHP6F5112V")
      (description "0805 0.51k ohm")
      (fields (field (name "MP") "ERJHP6F5112V"))
      (libsource (lib "BOT1_2025") (part "ERJHP6F5112V"))
    )
    (comp (ref "R26")
      (value "10K")
      (footprint "RESC2012X65N")
      (description "10k ohm 0805 smd resistor")
      (fields
        (field (name "MF") "{'manufacturer': u'Stackpole Electronics Inc'}")
        (field (name "MP") "RMCF0805FT10K0")
      )
      (libsource (lib "BOT1_2025") (part "RMCF0805FT10K0"))
    )
    (comp (ref "R27")
      (value "10K")
      (footprint "RESC2012X65N")
      (description "10k ohm 0805 smd resistor")
      (fields
        (field (name "MF") "{'manufacturer': u'Stackpole Electronics Inc'}")
        (field (name "MP") "RMCF0805FT10K0")
      )
      (libsource (lib "BOT1_2025") (part "RMCF0805FT10K0"))
    )
    (comp (ref "R28")
      (value "10K")
      (footprint "RESC2012X65N")
      (description "10k ohm 0805 smd resistor")
      (fields
        (field (name "MF") "{'manufacturer': u'Stackpole Electronics Inc'}")
        (field (name "MP") "RMCF0805FT10K0")
      )
      (libsource (lib "BOT1_2025") (part "RMCF0805FT10K0"))
    )
    (comp (ref "R29")
      (value "10K")
      (footprint "RESC2012X65N")
      (description "10k ohm 0805 smd resistor")
      (fields
        (field (name "MF") "{'manufacturer': u'Stackpole Electronics Inc'}")
        (field (name "MP") "RMCF0805FT10K0")
      )
      (libsource (lib "BOT1_2025") (part "RMCF0805FT10K0"))
    )
    (comp (ref "R30")
      (value "10K")
      (footprint "RESC2012X65N")
      (description "10k ohm 0805 smd resistor")
      (fields
        (field (name "MF") "{'manufacturer': u'Stackpole Electronics Inc'}")
        (field (name "MP") "RMCF0805FT10K0")
      )
      (libsource (lib "BOT1_2025") (part "RMCF0805FT10K0"))
    )
    (comp (ref "R31")
      (value "10K")
      (footprint "RESC2012X65N")
      (description "10k ohm 0805 smd resistor")
      (fields
        (field (name "MF") "{'manufacturer': u'Stackpole Electronics Inc'}")
        (field (name "MP") "RMCF0805FT10K0")
      )
      (libsource (lib "BOT1_2025") (part "RMCF0805FT10K0"))
    )
    (comp (ref "R32")
      (value "10K")
      (footprint "RESC2012X65N")
      (description "10k ohm 0805 smd resistor")
      (fields
        (field (name "MF") "{'manufacturer': u'Stackpole Electronics Inc'}")
        (field (name "MP") "RMCF0805FT10K0")
      )
      (libsource (lib "BOT1_2025") (part "RMCF0805FT10K0"))
    )
    (comp (ref "R33")
      (value "10K")
      (footprint "RESC2012X65N")
      (description "10k ohm 0805 smd resistor")
      (fields
        (field (name "MF") "{'manufacturer': u'Stackpole Electronics Inc'}")
        (field (name "MP") "RMCF0805FT10K0")
      )
      (libsource (lib "BOT1_2025") (part "RMCF0805FT10K0"))
    )
    (comp (ref "R34")
      (value "0.51K")
      (footprint "BOT1_2025:RES_ERJHP6F5112V")
      (description "0805 0.51k ohm")
      (fields (field (name "MP") "ERJHP6F5112V"))
      (libsource (lib "BOT1_2025") (part "ERJHP6F5112V"))
    )
    (comp (ref "R35")
      (value "0.51K")
      (footprint "BOT1_2025:RES_ERJHP6F5112V")
      (description "0805 0.51k ohm")
      (fields (field (name "MP") "ERJHP6F5112V"))
      (libsource (lib "BOT1_2025") (part "ERJHP6F5112V"))
    )
    (comp (ref "R36")
      (value "0.51K")
      (footprint "BOT1_2025:RES_ERJHP6F5112V")
      (description "0805 0.51k ohm")
      (fields (field (name "MP") "ERJHP6F5112V"))
      (libsource (lib "BOT1_2025") (part "ERJHP6F5112V"))
    )
    (comp (ref "R37")
      (value "0.51K")
      (footprint "BOT1_2025:RES_ERJHP6F5112V")
      (description "0805 0.51k ohm")
      (fields (field (name "MP") "ERJHP6F5112V"))
      (libsource (lib "BOT1_2025") (part "ERJHP6F5112V"))
    )
    (comp (ref "R38")
      (value "100ohm")
      (footprint "1kOhm Resistor")
      (libsource (lib "BOT1_2025") (part "1kOhm resistor"))
    )
    (comp (ref "R39")
      (value "10K")
      (footprint "RESC2012X65N")
      (description "10k ohm 0805 smd resistor")
      (fields
        (field (name "MF") "{'manufacturer': u'Stackpole Electronics Inc'}")
        (field (name "MP") "RMCF0805FT10K0")
      )
      (libsource (lib "BOT1_2025") (part "RMCF0805FT10K0"))
    )
    (comp (ref "R40")
      (value "10K")
      (footprint "RESC2012X65N")
      (description "10k ohm 0805 smd resistor")
      (fields
        (field (name "MF") "{'manufacturer': u'Stackpole Electronics Inc'}")
        (field (name "MP") "RMCF0805FT10K0")
      )
      (libsource (lib "BOT1_2025") (part "RMCF0805FT10K0"))
    )
    (comp (ref "R41")
      (value "10K")
      (footprint "RESC2012X65N")
      (description "10k ohm 0805 smd resistor")
      (fields
        (field (name "MF") "{'manufacturer': u'Stackpole Electronics Inc'}")
        (field (name "MP") "RMCF0805FT10K0")
      )
      (libsource (lib "BOT1_2025") (part "RMCF0805FT10K0"))
    )
    (comp (ref "R42")
      (value "10K")
      (footprint "RESC2012X65N")
      (description "10k ohm 0805 smd resistor")
      (fields
        (field (name "MF") "{'manufacturer': u'Stackpole Electronics Inc'}")
        (field (name "MP") "RMCF0805FT10K0")
      )
      (libsource (lib "BOT1_2025") (part "RMCF0805FT10K0"))
    )
    (comp (ref "R43")
      (value "10K")
      (footprint "RESC2012X65N")
      (description "10k ohm 0805 smd resistor")
      (fields
        (field (name "MF") "{'manufacturer': u'Stackpole Electronics Inc'}")
        (field (name "MP") "RMCF0805FT10K0")
      )
      (libsource (lib "BOT1_2025") (part "RMCF0805FT10K0"))
    )
    (comp (ref "R44")
      (value "10K")
      (footprint "RESC2012X65N")
      (description "10k ohm 0805 smd resistor")
      (fields
        (field (name "MF") "{'manufacturer': u'Stackpole Electronics Inc'}")
        (field (name "MP") "RMCF0805FT10K0")
      )
      (libsource (lib "BOT1_2025") (part "RMCF0805FT10K0"))
    )
    (comp (ref "R45")
      (value "10K")
      (footprint "RESC2012X65N")
      (description "10k ohm 0805 smd resistor")
      (fields
        (field (name "MF") "{'manufacturer': u'Stackpole Electronics Inc'}")
        (field (name "MP") "RMCF0805FT10K0")
      )
      (libsource (lib "BOT1_2025") (part "RMCF0805FT10K0"))
    )
    (comp (ref "R46")
      (value "10K")
      (footprint "RESC2012X65N")
      (description "10k ohm 0805 smd resistor")
      (fields
        (field (name "MF") "{'manufacturer': u'Stackpole Electronics Inc'}")
        (field (name "MP") "RMCF0805FT10K0")
      )
      (libsource (lib "BOT1_2025") (part "RMCF0805FT10K0"))
    )
    (comp (ref "R47")
      (value "100ohm")
      (footprint "1kOhm Resistor")
      (libsource (lib "BOT1_2025") (part "1kOhm resistor"))
    )
    (comp (ref "R48")
      (value "0.51K")
      (footprint "BOT1_2025:RES_ERJHP6F5112V")
      (description "0805 0.51k ohm")
      (fields (field (name "MP") "ERJHP6F5112V"))
      (libsource (lib "BOT1_2025") (part "ERJHP6F5112V"))
    )
    (comp (ref "R49")
      (value "0.51K")
      (footprint "BOT1_2025:RES_ERJHP6F5112V")
      (description "0805 0.51k ohm")
      (fields (field (name "MP") "ERJHP6F5112V"))
      (libsource (lib "BOT1_2025") (part "ERJHP6F5112V"))
    )
    (comp (ref "R50")
      (value "0.51K")
      (footprint "BOT1_2025:RES_ERJHP6F5112V")
      (description "0805 0.51k ohm")
      (fields (field (name "MP") "ERJHP6F5112V"))
      (libsource (lib "BOT1_2025") (part "ERJHP6F5112V"))
    )
    (comp (ref "R51")
      (value "0.51K")
      (footprint "BOT1_2025:RES_ERJHP6F5112V")
      (description "0805 0.51k ohm")
      (fields (field (name "MP") "ERJHP6F5112V"))
      (libsource (lib "BOT1_2025") (part "ERJHP6F5112V"))
    )
    (comp (ref "S1")
      (value "PTS647SK38SMTR2LFS")
      (footprint "PTS647SK38SMTR2LFS")
      (description "Tactile Switch SPST-NO Top Actuated Surface Mount")
      (fields (field (name "MF") "C&K") (field (name "MP") "PTS 647 SK38 SMTR2 LFS"))
      (libsource (lib "BOT1_2025") (part "PTS647SK38SMTR2LFS"))
    )
    (comp (ref "S2")
      (value "PTS647SK38SMTR2LFS")
      (footprint "PTS647SK38SMTR2LFS")
      (description "Tactile Switch SPST-NO Top Actuated Surface Mount")
      (fields (field (name "MF") "C&K") (field (name "MP") "PTS 647 SK38 SMTR2 LFS"))
      (libsource (lib "BOT1_2025") (part "PTS647SK38SMTR2LFS"))
    )
    (comp (ref "S3")
      (value "PTS647SK38SMTR2LFS")
      (footprint "PTS647SK38SMTR2LFS")
      (description "Tactile Switch SPST-NO Top Actuated Surface Mount")
      (fields (field (name "MF") "C&K") (field (name "MP") "PTS 647 SK38 SMTR2 LFS"))
      (libsource (lib "BOT1_2025") (part "PTS647SK38SMTR2LFS"))
    )
    (comp (ref "S4")
      (value "PTS647SK38SMTR2LFS")
      (footprint "PTS647SK38SMTR2LFS")
      (description "Tactile Switch SPST-NO Top Actuated Surface Mount")
      (fields (field (name "MF") "C&K") (field (name "MP") "PTS 647 SK38 SMTR2 LFS"))
      (libsource (lib "BOT1_2025") (part "PTS647SK38SMTR2LFS"))
    )
    (comp (ref "S5")
      (value "PTS647SK38SMTR2LFS")
      (footprint "PTS647SK38SMTR2LFS")
      (description "Tactile Switch SPST-NO Top Actuated Surface Mount")
      (fields (field (name "MF") "C&K") (field (name "MP") "PTS 647 SK38 SMTR2 LFS"))
      (libsource (lib "BOT1_2025") (part "PTS647SK38SMTR2LFS"))
    )
    (comp (ref "S6")
      (value "PTS647SK38SMTR2LFS")
      (footprint "PTS647SK38SMTR2LFS")
      (description "Tactile Switch SPST-NO Top Actuated Surface Mount")
      (fields (field (name "MF") "C&K") (field (name "MP") "PTS 647 SK38 SMTR2 LFS"))
      (libsource (lib "BOT1_2025") (part "PTS647SK38SMTR2LFS"))
    )
    (comp (ref "S7")
      (value "PTS647SK38SMTR2LFS")
      (footprint "PTS647SK38SMTR2LFS")
      (description "Tactile Switch SPST-NO Top Actuated Surface Mount")
      (fields (field (name "MF") "C&K") (field (name "MP") "PTS 647 SK38 SMTR2 LFS"))
      (libsource (lib "BOT1_2025") (part "PTS647SK38SMTR2LFS"))
    )
    (comp (ref "S8")
      (value "PTS647SK38SMTR2LFS")
      (footprint "PTS647SK38SMTR2LFS")
      (description "Tactile Switch SPST-NO Top Actuated Surface Mount")
      (fields (field (name "MF") "C&K") (field (name "MP") "PTS 647 SK38 SMTR2 LFS"))
      (libsource (lib "BOT1_2025") (part "PTS647SK38SMTR2LFS"))
    )
    (comp (ref "S9")
      (value "PTS647SK38SMTR2LFS")
      (footprint "PTS647SK38SMTR2LFS")
      (description "Tactile Switch SPST-NO Top Actuated Surface Mount")
      (fields (field (name "MF") "C&K") (field (name "MP") "PTS 647 SK38 SMTR2 LFS"))
      (libsource (lib "BOT1_2025") (part "PTS647SK38SMTR2LFS"))
    )
    (comp (ref "S10")
      (value "PTS647SK38SMTR2LFS")
      (footprint "PTS647SK38SMTR2LFS")
      (description "Tactile Switch SPST-NO Top Actuated Surface Mount")
      (fields (field (name "MF") "C&K") (field (name "MP") "PTS 647 SK38 SMTR2 LFS"))
      (libsource (lib "BOT1_2025") (part "PTS647SK38SMTR2LFS"))
    )
    (comp (ref "S11")
      (value "PTS647SK38SMTR2LFS")
      (footprint "PTS647SK38SMTR2LFS")
      (description "Tactile Switch SPST-NO Top Actuated Surface Mount")
      (fields (field (name "MF") "C&K") (field (name "MP") "PTS 647 SK38 SMTR2 LFS"))
      (libsource (lib "BOT1_2025") (part "PTS647SK38SMTR2LFS"))
    )
    (comp (ref "S12")
      (value "PTS647SK38SMTR2LFS")
      (footprint "PTS647SK38SMTR2LFS")
      (description "Tactile Switch SPST-NO Top Actuated Surface Mount")
      (fields (field (name "MF") "C&K") (field (name "MP") "PTS 647 SK38 SMTR2 LFS"))
      (libsource (lib "BOT1_2025") (part "PTS647SK38SMTR2LFS"))
    )
    (comp (ref "S13")
      (value "PTS647SK38SMTR2LFS")
      (footprint "PTS647SK38SMTR2LFS")
      (description "Tactile Switch SPST-NO Top Actuated Surface Mount")
      (fields (field (name "MF") "C&K") (field (name "MP") "PTS 647 SK38 SMTR2 LFS"))
      (libsource (lib "BOT1_2025") (part "PTS647SK38SMTR2LFS"))
    )
    (comp (ref "S14")
      (value "PTS647SK38SMTR2LFS")
      (footprint "PTS647SK38SMTR2LFS")
      (description "Tactile Switch SPST-NO Top Actuated Surface Mount")
      (fields (field (name "MF") "C&K") (field (name "MP") "PTS 647 SK38 SMTR2 LFS"))
      (libsource (lib "BOT1_2025") (part "PTS647SK38SMTR2LFS"))
    )
    (comp (ref "S15")
      (value "PTS647SK38SMTR2LFS")
      (footprint "PTS647SK38SMTR2LFS")
      (description "Tactile Switch SPST-NO Top Actuated Surface Mount")
      (fields (field (name "MF") "C&K") (field (name "MP") "PTS 647 SK38 SMTR2 LFS"))
      (libsource (lib "BOT1_2025") (part "PTS647SK38SMTR2LFS"))
    )
    (comp (ref "S16")
      (value "PTS647SK38SMTR2LFS")
      (footprint "PTS647SK38SMTR2LFS")
      (description "Tactile Switch SPST-NO Top Actuated Surface Mount")
      (fields (field (name "MF") "C&K") (field (name "MP") "PTS 647 SK38 SMTR2 LFS"))
      (libsource (lib "BOT1_2025") (part "PTS647SK38SMTR2LFS"))
    )
    (comp (ref "SW1")
      (value "Slide Switch")
      (footprint "Slide Switch")
      (libsource (lib "R1") (part "Slide Switch"))
    )
    (comp (ref "sw2")
      (value "Push Button 7x7_1")
      (footprint "Push Button 7x7")
      (libsource (lib "BOT1_2025") (part "Push Button 7x7_1"))
    )
    (comp (ref "U1")
      (value "BTN8982TA")
      (footprint "BTN8982 Motor driver")
      (description "Motor / Motion / Ignition Controllers & Drivers TRILITH IC / NOVALITH IC")
      (fields (field (name "MF") "Infineon Technologies"))
      (libsource (lib "BOT1_2025") (part "BTN8982TA"))
    )
    (comp (ref "U2")
      (value "BTN8982TA")
      (footprint "BTN8982 Motor driver")
      (description "Motor / Motion / Ignition Controllers & Drivers TRILITH IC / NOVALITH IC")
      (fields (field (name "MF") "Infineon Technologies"))
      (libsource (lib "BOT1_2025") (part "BTN8982TA"))
    )
    (comp (ref "U3")
      (value "BTN8982TA")
      (footprint "BTN8982 Motor driver")
      (description "Motor / Motion / Ignition Controllers & Drivers TRILITH IC / NOVALITH IC")
      (fields (field (name "MF") "Infineon Technologies"))
      (libsource (lib "BOT1_2025") (part "BTN8982TA"))
    )
    (comp (ref "U4")
      (value "BTN8982TA")
      (footprint "BTN8982 Motor driver")
      (description "Motor / Motion / Ignition Controllers & Drivers TRILITH IC / NOVALITH IC")
      (fields (field (name "MF") "Infineon Technologies"))
      (libsource (lib "BOT1_2025") (part "BTN8982TA"))
    )
    (comp (ref "U5")
      (value "PCA9685 module")
      (footprint "PCA9685 module")
      (description "Undefined or Miscellaneous")
      (fields (field (name "MANUFACTURER_PART_NUMBER") "815") (field (name "MOUSER PART NUMBER") "485-815"))
      (libsource (lib "BOT1_2025") (part "PCA9685 module"))
    )
    (comp (ref "U6")
      (value "BTN8982TA")
      (footprint "BTN8982 Motor driver")
      (description "Motor / Motion / Ignition Controllers & Drivers TRILITH IC / NOVALITH IC")
      (fields (field (name "MF") "Infineon Technologies"))
      (libsource (lib "BOT1_2025") (part "BTN8982TA"))
    )
    (comp (ref "U7")
      (value "BTN8982TA")
      (footprint "BTN8982 Motor driver")
      (description "Motor / Motion / Ignition Controllers & Drivers TRILITH IC / NOVALITH IC")
      (fields (field (name "MF") "Infineon Technologies"))
      (libsource (lib "BOT1_2025") (part "BTN8982TA"))
    )
    (comp (ref "U8")
      (value "BTN8982TA")
      (footprint "BTN8982 Motor driver")
      (description "Motor / Motion / Ignition Controllers & Drivers TRILITH IC / NOVALITH IC")
      (fields (field (name "MF") "Infineon Technologies"))
      (libsource (lib "BOT1_2025") (part "BTN8982TA"))
    )
    (comp (ref "U9")
      (value "BTN8982TA")
      (footprint "BTN8982 Motor driver")
      (description "Motor / Motion / Ignition Controllers & Drivers TRILITH IC / NOVALITH IC")
      (fields (field (name "MF") "Infineon Technologies"))
      (libsource (lib "BOT1_2025") (part "BTN8982TA"))
    )
    (comp (ref "U10")
      (value "BTN8982TA")
      (footprint "BTN8982 Motor driver")
      (description "Motor / Motion / Ignition Controllers & Drivers TRILITH IC / NOVALITH IC")
      (fields (field (name "MF") "Infineon Technologies"))
      (libsource (lib "BOT1_2025") (part "BTN8982TA"))
    )
    (comp (ref "U11")
      (value "BTN8982TA")
      (footprint "BTN8982 Motor driver")
      (description "Motor / Motion / Ignition Controllers & Drivers TRILITH IC / NOVALITH IC")
      (fields (field (name "MF") "Infineon Technologies"))
      (libsource (lib "BOT1_2025") (part "BTN8982TA"))
    )
    (comp (ref "U12")
      (value "BTN8982TA")
      (footprint "BTN8982 Motor driver")
      (description "Motor / Motion / Ignition Controllers & Drivers TRILITH IC / NOVALITH IC")
      (fields (field (name "MF") "Infineon Technologies"))
      (libsource (lib "BOT1_2025") (part "BTN8982TA"))
    )
    (comp (ref "U13")
      (value "BTN8982TA")
      (footprint "BTN8982 Motor driver")
      (description "Motor / Motion / Ignition Controllers & Drivers TRILITH IC / NOVALITH IC")
      (fields (field (name "MF") "Infineon Technologies"))
      (libsource (lib "BOT1_2025") (part "BTN8982TA"))
    )
    (comp (ref "U14")
      (value "Teensy 41v")
      (footprint "Teensy 41v")
      (description "RT1062 Teensy 4.1 series ARMÂ® CortexÂ®-M7 MPU Embedded Evaluation Board")
      (fields (field (name "MP") "DEV-16771") (field (name "MF") "SparkFun Electronics"))
      (libsource (lib "BOT1_2025") (part "Teensy 41v"))
    )
    (comp (ref "U15")
      (value "BNO-055")
      (footprint "BNO-055")
      (description "Adafruit 9-DOF Absolute Orientation IMU Fusion Breakout - BNO055 ¦ Adafruit Industries 2472")
      (fields (field (name "MF") "Adafruit") (field (name "MP") "2472"))
      (libsource (lib "BOT1_2025") (part "BNO-055"))
    )
    (comp (ref "U16")
      (value "BTN8982TA")
      (footprint "BTN8982 Motor driver")
      (description "Motor / Motion / Ignition Controllers & Drivers TRILITH IC / NOVALITH IC")
      (fields (field (name "MF") "Infineon Technologies"))
      (libsource (lib "BOT1_2025") (part "BTN8982TA"))
    )
    (comp (ref "U17")
      (value "BTN8982TA")
      (footprint "BTN8982 Motor driver")
      (description "Motor / Motion / Ignition Controllers & Drivers TRILITH IC / NOVALITH IC")
      (fields (field (name "MF") "Infineon Technologies"))
      (libsource (lib "BOT1_2025") (part "BTN8982TA"))
    )
    (comp (ref "U18")
      (value "BTN8982TA")
      (footprint "BTN8982 Motor driver")
      (description "Motor / Motion / Ignition Controllers & Drivers TRILITH IC / NOVALITH IC")
      (fields (field (name "MF") "Infineon Technologies"))
      (libsource (lib "BOT1_2025") (part "BTN8982TA"))
    )
    (comp (ref "U19")
      (value "BTN8982TA")
      (footprint "BTN8982 Motor driver")
      (description "Motor / Motion / Ignition Controllers & Drivers TRILITH IC / NOVALITH IC")
      (fields (field (name "MF") "Infineon Technologies"))
      (libsource (lib "BOT1_2025") (part "BTN8982TA"))
    )
  )
  (nets
    (net (code "1") (name "+3V3") (class "Default")
      (node (ref "*5") (pin "3") (pinfunction "LV_3") (pintype "power_in"))
      (node (ref "Buck2") (pin "OUT+") (pinfunction "OUT+_OUT+") (pintype "power_in"))
      (node (ref "E1") (pin "1") (pintype "passive"))
      (node (ref "E2") (pin "1") (pintype "passive"))
      (node (ref "E3") (pin "1") (pintype "passive"))
      (node (ref "E4") (pin "1") (pintype "passive"))
      (node (ref "J30") (pin "3") (pinfunction "3_3") (pintype "passive"))
      (node (ref "U15") (pin "1") (pinfunction "VIN_1") (pintype "input"))
      (node (ref "U5") (pin "50") (pinfunction "VCC_1_50") (pintype "passive"))
    )
    (net (code "2") (name "+5") (class "Default")
      (node (ref "*5") (pin "10") (pinfunction "HV_10") (pintype "power_in"))
      (node (ref "Buck4") (pin "OUT+") (pinfunction "OUT+_OUT+") (pintype "power_in"))
      (node (ref "E5") (pin "1") (pintype "passive"))
      (node (ref "E6") (pin "1") (pintype "passive"))
      (node (ref "J30") (pin "2") (pinfunction "2_2") (pintype "passive"))
    )
    (net (code "3") (name "+5V") (class "Default")
      (node (ref "SW1") (pin "1") (pinfunction "NC_1") (pintype "passive"))
      (node (ref "U14") (pin "VIN") (pinfunction "VIN_VIN") (pintype "input"))
    )
    (net (code "4") (name "+6") (class "Default")
      (node (ref "J1") (pin "2") (pintype "passive"))
      (node (ref "J11") (pin "1") (pinfunction "POS_1") (pintype "power_in"))
      (node (ref "J2") (pin "2") (pintype "passive"))
      (node (ref "J22") (pin "10") (pinfunction "10_10") (pintype "passive"))
      (node (ref "J5") (pin "2") (pintype "passive"))
      (node (ref "J6") (pin "2") (pintype "passive"))
      (node (ref "J7") (pin "2") (pintype "passive"))
      (node (ref "J8") (pin "2") (pintype "passive"))
    )
    (net (code "5") (name "+12") (class "Default")
      (node (ref "J14") (pin "8") (pinfunction "8_8") (pintype "passive"))
      (node (ref "J16") (pin "1") (pinfunction "POS_1") (pintype "power_in"))
      (node (ref "J30") (pin "1") (pinfunction "1_1") (pintype "passive"))
      (node (ref "J9") (pin "8") (pinfunction "8_8") (pintype "passive"))
    )
    (net (code "6") (name "/COM") (class "Default")
      (node (ref "Buck1") (pin "OUT+") (pinfunction "OUT+_OUT+") (pintype "power_in"))
      (node (ref "SW1") (pin "2") (pinfunction "COM_2") (pintype "passive"))
    )
    (net (code "7") (name "/D1_N") (class "Default")
      (node (ref "J23") (pin "02") (pinfunction "D-_02") (pintype "bidirectional"))
      (node (ref "U14") (pin "D-") (pinfunction "D-_D-") (pintype "bidirectional"))
    )
    (net (code "8") (name "/D1_P") (class "Default")
      (node (ref "J23") (pin "03") (pinfunction "D+_03") (pintype "bidirectional"))
      (node (ref "U14") (pin "D+") (pinfunction "D+_D+") (pintype "bidirectional"))
    )
    (net (code "9") (name "/DW1H_A") (class "Default")
      (node (ref "*5") (pin "12") (pinfunction "HV1_12") (pintype "bidirectional"))
      (node (ref "E5") (pin "3") (pintype "passive"))
    )
    (net (code "10") (name "/DW1H_B") (class "Default")
      (node (ref "*5") (pin "11") (pinfunction "HV2_11") (pintype "bidirectional"))
      (node (ref "E5") (pin "4") (pintype "passive"))
    )
    (net (code "11") (name "/DW1L_A") (class "Default")
      (node (ref "*5") (pin "1") (pinfunction "LV1_1") (pintype "bidirectional"))
      (node (ref "U14") (pin "30") (pinfunction "CRX3_30") (pintype "bidirectional"))
    )
    (net (code "12") (name "/DW1L_B") (class "Default")
      (node (ref "*5") (pin "2") (pinfunction "LV2_2") (pintype "bidirectional"))
      (node (ref "U14") (pin "31") (pinfunction "CTX3_31") (pintype "bidirectional"))
    )
    (net (code "13") (name "/DW2H_A") (class "Default")
      (node (ref "*5") (pin "8") (pinfunction "HV3_8") (pintype "bidirectional"))
      (node (ref "E6") (pin "4") (pintype "passive"))
    )
    (net (code "14") (name "/DW2H_B") (class "Default")
      (node (ref "*5") (pin "7") (pinfunction "HV4_7") (pintype "bidirectional"))
      (node (ref "E6") (pin "3") (pintype "passive"))
    )
    (net (code "15") (name "/DW2L_A") (class "Default")
      (node (ref "*5") (pin "5") (pinfunction "LV3_5") (pintype "bidirectional"))
      (node (ref "U14") (pin "29") (pinfunction "TX7_29") (pintype "bidirectional"))
    )
    (net (code "16") (name "/DW2L_B") (class "Default")
      (node (ref "*5") (pin "6") (pinfunction "LV4_6") (pintype "bidirectional"))
      (node (ref "U14") (pin "28") (pinfunction "RX7_28") (pintype "bidirectional"))
    )
    (net (code "17") (name "/E1_ChA") (class "Default")
      (node (ref "E1") (pin "3") (pintype "passive"))
      (node (ref "U14") (pin "20") (pinfunction "A6_20") (pintype "bidirectional"))
    )
    (net (code "18") (name "/E1_ChB") (class "Default")
      (node (ref "E1") (pin "4") (pintype "passive"))
      (node (ref "U14") (pin "21") (pinfunction "A7_21") (pintype "bidirectional"))
    )
    (net (code "19") (name "/E2_ChA") (class "Default")
      (node (ref "E2") (pin "3") (pintype "passive"))
      (node (ref "U14") (pin "27") (pinfunction "A13_27") (pintype "bidirectional"))
    )
    (net (code "20") (name "/E2_ChB") (class "Default")
      (node (ref "E2") (pin "4") (pintype "passive"))
      (node (ref "U14") (pin "26") (pinfunction "A12_26") (pintype "bidirectional"))
    )
    (net (code "21") (name "/E3_ChA") (class "Default")
      (node (ref "E3") (pin "4") (pintype "passive"))
      (node (ref "U14") (pin "41") (pinfunction "A17_41") (pintype "bidirectional"))
    )
    (net (code "22") (name "/E3_ChB") (class "Default")
      (node (ref "E3") (pin "3") (pintype "passive"))
      (node (ref "U14") (pin "40") (pinfunction "A16_40") (pintype "bidirectional"))
    )
    (net (code "23") (name "/E4_ChA") (class "Default")
      (node (ref "E4") (pin "3") (pintype "passive"))
      (node (ref "U14") (pin "33") (pinfunction "MCLK2_33") (pintype "bidirectional"))
    )
    (net (code "24") (name "/E4_ChB") (class "Default")
      (node (ref "E4") (pin "4") (pintype "passive"))
      (node (ref "U14") (pin "32") (pinfunction "OUT1B_32") (pintype "bidirectional"))
    )
    (net (code "25") (name "/EN_1") (class "Default")
      (node (ref "J17") (pin "1") (pinfunction "POS_1") (pintype "power_in"))
      (node (ref "J18") (pin "1") (pinfunction "POS_1") (pintype "power_in"))
      (node (ref "J3") (pin "1") (pinfunction "POS_1") (pintype "power_in"))
      (node (ref "J4") (pin "2") (pinfunction "NEG_2") (pintype "power_in"))
      (node (ref "R1") (pin "2") (pinfunction "2_2") (pintype "passive"))
    )
    (net (code "26") (name "/In1") (class "Default")
      (node (ref "J30") (pin "4") (pinfunction "4_4") (pintype "passive"))
      (node (ref "U5") (pin "8") (pinfunction "PWM7_8") (pintype "passive"))
    )
    (net (code "27") (name "/In2") (class "Default")
      (node (ref "J30") (pin "5") (pinfunction "5_5") (pintype "passive"))
      (node (ref "U5") (pin "7") (pinfunction "PWM6_7") (pintype "passive"))
    )
    (net (code "28") (name "/In3") (class "Default")
      (node (ref "J30") (pin "6") (pinfunction "6_6") (pintype "passive"))
      (node (ref "U5") (pin "6") (pinfunction "PWM5_6") (pintype "passive"))
    )
    (net (code "29") (name "/In4") (class "Default")
      (node (ref "J30") (pin "7") (pinfunction "7_7") (pintype "passive"))
      (node (ref "U5") (pin "5") (pinfunction "PWM4_5") (pintype "passive"))
    )
    (net (code "30") (name "/In5") (class "Default")
      (node (ref "J30") (pin "8") (pinfunction "8_8") (pintype "passive"))
      (node (ref "U5") (pin "4") (pinfunction "PWM3_4") (pintype "passive"))
    )
    (net (code "31") (name "/In6") (class "Default")
      (node (ref "J30") (pin "9") (pinfunction "9_9") (pintype "passive"))
      (node (ref "U5") (pin "3") (pinfunction "PWM2_3") (pintype "passive"))
    )
    (net (code "32") (name "/In7") (class "Default")
      (node (ref "J30") (pin "10") (pinfunction "10_10") (pintype "passive"))
      (node (ref "U5") (pin "2") (pinfunction "PWM1_2") (pintype "passive"))
    )
    (net (code "33") (name "/In8") (class "Default")
      (node (ref "J30") (pin "11") (pinfunction "11_11") (pintype "passive"))
      (node (ref "U5") (pin "1") (pinfunction "PWM0_1") (pintype "passive"))
    )
    (net (code "34") (name "/LED1") (class "Default")
      (node (ref "J24") (pin "3") (pinfunction "3_3") (pintype "passive"))
      (node (ref "J28") (pin "SH2") (pinfunction "SHIELD_SH2") (pintype "passive"))
    )
    (net (code "35") (name "/LS1") (class "Default")
      (node (ref "LS1") (pin "1") (pinfunction "1_1") (pintype "passive"))
      (node (ref "U14") (pin "8") (pinfunction "TX2_8") (pintype "bidirectional"))
    )
    (net (code "36") (name "/LS2") (class "Default")
      (node (ref "LS2") (pin "1") (pinfunction "1_1") (pintype "passive"))
      (node (ref "U14") (pin "9") (pinfunction "OUT1C_9") (pintype "bidirectional"))
    )
    (net (code "37") (name "/LS3") (class "Default")
      (node (ref "LS3") (pin "1") (pinfunction "1_1") (pintype "passive"))
      (node (ref "U14") (pin "10") (pinfunction "CS1_10") (pintype "bidirectional"))
    )
    (net (code "38") (name "/LS4") (class "Default")
      (node (ref "LS4") (pin "1") (pinfunction "1_1") (pintype "passive"))
      (node (ref "U14") (pin "11") (pinfunction "MOSI_11") (pintype "bidirectional"))
    )
    (net (code "39") (name "/M1A") (class "Default")
      (node (ref "C11") (pin "2") (pinfunction "2_2") (pintype "passive"))
      (node (ref "C3") (pin "1") (pinfunction "1_1") (pintype "passive"))
      (node (ref "J12") (pin "1") (pinfunction "POS_1") (pintype "power_in"))
      (node (ref "U1") (pin "4") (pinfunction "OUT_4") (pintype "power_in"))
    )
    (net (code "40") (name "/M1B") (class "Default")
      (node (ref "C12") (pin "2") (pinfunction "2_2") (pintype "passive"))
      (node (ref "C4") (pin "1") (pinfunction "1_1") (pintype "passive"))
      (node (ref "J12") (pin "2") (pinfunction "NEG_2") (pintype "power_in"))
      (node (ref "U2") (pin "4") (pinfunction "OUT_4") (pintype "power_in"))
    )
    (net (code "41") (name "/M1_In1") (class "Default")
      (node (ref "MD1") (pin "3") (pintype "passive"))
      (node (ref "R2") (pin "1") (pinfunction "1_1") (pintype "passive"))
      (node (ref "S3") (pin "2") (pinfunction "NO_2_2") (pintype "bidirectional"))
      (node (ref "U14") (pin "2") (pinfunction "OUT2_2") (pintype "bidirectional"))
    )
    (net (code "42") (name "/M1_In2") (class "Default")
      (node (ref "MD1") (pin "4") (pinfunction "4_4") (pintype "passive"))
      (node (ref "R4") (pin "1") (pinfunction "1_1") (pintype "passive"))
      (node (ref "S15") (pin "2") (pinfunction "NO_2_2") (pintype "bidirectional"))
      (node (ref "U14") (pin "3") (pinfunction "LRCLK2_3") (pintype "bidirectional"))
    )
    (net (code "43") (name "/M2A") (class "Default")
      (node (ref "C21") (pin "1") (pinfunction "1_1") (pintype "passive"))
      (node (ref "C29") (pin "2") (pinfunction "2_2") (pintype "passive"))
      (node (ref "J13") (pin "1") (pinfunction "POS_1") (pintype "power_in"))
      (node (ref "U6") (pin "4") (pinfunction "OUT_4") (pintype "power_in"))
    )
    (net (code "44") (name "/M2B") (class "Default")
      (node (ref "C22") (pin "1") (pinfunction "1_1") (pintype "passive"))
      (node (ref "C30") (pin "2") (pinfunction "2_2") (pintype "passive"))
      (node (ref "J13") (pin "2") (pinfunction "NEG_2") (pintype "power_in"))
      (node (ref "U7") (pin "4") (pinfunction "OUT_4") (pintype "power_in"))
    )
    (net (code "45") (name "/M2_In1") (class "Default")
      (node (ref "MD1") (pin "1") (pintype "passive"))
      (node (ref "R14") (pin "1") (pinfunction "1_1") (pintype "passive"))
      (node (ref "S4") (pin "2") (pinfunction "NO_2_2") (pintype "bidirectional"))
      (node (ref "U14") (pin "0") (pinfunction "RX1_0") (pintype "bidirectional"))
    )
    (net (code "46") (name "/M2_In2") (class "Default")
      (node (ref "MD1") (pin "2") (pintype "passive"))
      (node (ref "R16") (pin "1") (pinfunction "1_1") (pintype "passive"))
      (node (ref "S16") (pin "2") (pinfunction "NO_2_2") (pintype "bidirectional"))
      (node (ref "U14") (pin "1") (pinfunction "TX1_1") (pintype "bidirectional"))
    )
    (net (code "47") (name "/M3A") (class "Default")
      (node (ref "C13") (pin "2") (pinfunction "2_2") (pintype "passive"))
      (node (ref "C5") (pin "1") (pinfunction "1_1") (pintype "passive"))
      (node (ref "J20") (pin "1") (pinfunction "POS_1") (pintype "power_in"))
      (node (ref "U3") (pin "4") (pinfunction "OUT_4") (pintype "power_in"))
    )
    (net (code "48") (name "/M3B") (class "Default")
      (node (ref "C14") (pin "2") (pinfunction "2_2") (pintype "passive"))
      (node (ref "C6") (pin "1") (pinfunction "1_1") (pintype "passive"))
      (node (ref "J20") (pin "2") (pinfunction "NEG_2") (pintype "power_in"))
      (node (ref "U4") (pin "4") (pinfunction "OUT_4") (pintype "power_in"))
    )
    (net (code "49") (name "/M3_In1") (class "Default")
      (node (ref "MD2") (pin "3") (pintype "passive"))
      (node (ref "R6") (pin "1") (pinfunction "1_1") (pintype "passive"))
      (node (ref "S5") (pin "2") (pinfunction "NO_2_2") (pintype "bidirectional"))
      (node (ref "U14") (pin "6") (pinfunction "OUT1D_6") (pintype "bidirectional"))
    )
    (net (code "50") (name "/M3_In2") (class "Default")
      (node (ref "MD2") (pin "4") (pinfunction "4_4") (pintype "passive"))
      (node (ref "R8") (pin "1") (pinfunction "1_1") (pintype "passive"))
      (node (ref "S9") (pin "2") (pinfunction "NO_2_2") (pintype "bidirectional"))
      (node (ref "U14") (pin "7") (pinfunction "RX2_7") (pintype "bidirectional"))
    )
    (net (code "51") (name "/M4A") (class "Default")
      (node (ref "C23") (pin "1") (pinfunction "1_1") (pintype "passive"))
      (node (ref "C31") (pin "2") (pinfunction "2_2") (pintype "passive"))
      (node (ref "J21") (pin "1") (pinfunction "POS_1") (pintype "power_in"))
      (node (ref "U8") (pin "4") (pinfunction "OUT_4") (pintype "power_in"))
    )
    (net (code "52") (name "/M4B") (class "Default")
      (node (ref "C24") (pin "1") (pinfunction "1_1") (pintype "passive"))
      (node (ref "C32") (pin "2") (pinfunction "2_2") (pintype "passive"))
      (node (ref "J21") (pin "2") (pinfunction "NEG_2") (pintype "power_in"))
      (node (ref "U9") (pin "4") (pinfunction "OUT_4") (pintype "power_in"))
    )
    (net (code "53") (name "/M4_In1") (class "Default")
      (node (ref "MD2") (pin "1") (pintype "passive"))
      (node (ref "R18") (pin "1") (pinfunction "1_1") (pintype "passive"))
      (node (ref "S1") (pin "2") (pinfunction "NO_2_2") (pintype "bidirectional"))
      (node (ref "U14") (pin "4") (pinfunction "BCLK2_4") (pintype "bidirectional"))
    )
    (net (code "54") (name "/M4_In2") (class "Default")
      (node (ref "MD2") (pin "2") (pintype "passive"))
      (node (ref "R20") (pin "1") (pinfunction "1_1") (pintype "passive"))
      (node (ref "S10") (pin "2") (pinfunction "NO_2_2") (pintype "bidirectional"))
      (node (ref "U14") (pin "5") (pinfunction "IN2_5") (pintype "bidirectional"))
    )
    (net (code "55") (name "/M5A") (class "Default")
      (node (ref "C39") (pin "1") (pinfunction "1_1") (pintype "passive"))
      (node (ref "C47") (pin "2") (pinfunction "2_2") (pintype "passive"))
      (node (ref "J25") (pin "1") (pinfunction "POS_1") (pintype "power_in"))
      (node (ref "U10") (pin "4") (pinfunction "OUT_4") (pintype "power_in"))
    )
    (net (code "56") (name "/M5B") (class "Default")
      (node (ref "C40") (pin "1") (pinfunction "1_1") (pintype "passive"))
      (node (ref "C48") (pin "2") (pinfunction "2_2") (pintype "passive"))
      (node (ref "J25") (pin "2") (pinfunction "NEG_2") (pintype "power_in"))
      (node (ref "U11") (pin "4") (pinfunction "OUT_4") (pintype "power_in"))
    )
    (net (code "57") (name "/M5_In1") (class "Default")
      (node (ref "MD3") (pin "4") (pinfunction "4_4") (pintype "passive"))
      (node (ref "R33") (pin "1") (pinfunction "1_1") (pintype "passive"))
      (node (ref "S2") (pin "2") (pinfunction "NO_2_2") (pintype "bidirectional"))
      (node (ref "U14") (pin "36") (pinfunction "CS2_36") (pintype "bidirectional"))
    )
    (net (code "58") (name "/M5_In2") (class "Default")
      (node (ref "MD3") (pin "3") (pintype "passive"))
      (node (ref "R27") (pin "1") (pinfunction "1_1") (pintype "passive"))
      (node (ref "S11") (pin "2") (pinfunction "NO_2_2") (pintype "bidirectional"))
      (node (ref "U14") (pin "37") (pinfunction "CS3_37") (pintype "bidirectional"))
    )
    (net (code "59") (name "/M6A") (class "Default")
      (node (ref "C57") (pin "1") (pinfunction "1_1") (pintype "passive"))
      (node (ref "C63") (pin "2") (pinfunction "2_2") (pintype "passive"))
      (node (ref "J29") (pin "1") (pinfunction "POS_1") (pintype "power_in"))
      (node (ref "U16") (pin "4") (pinfunction "OUT_4") (pintype "power_in"))
    )
    (net (code "60") (name "/M6B") (class "Default")
      (node (ref "C58") (pin "1") (pinfunction "1_1") (pintype "passive"))
      (node (ref "C64") (pin "2") (pinfunction "2_2") (pintype "passive"))
      (node (ref "J29") (pin "2") (pinfunction "NEG_2") (pintype "power_in"))
      (node (ref "U17") (pin "4") (pinfunction "OUT_4") (pintype "power_in"))
    )
    (net (code "61") (name "/M6_In1") (class "Default")
      (node (ref "MD3") (pin "2") (pintype "passive"))
      (node (ref "R42") (pin "1") (pinfunction "1_1") (pintype "passive"))
      (node (ref "S6") (pin "2") (pinfunction "NO_2_2") (pintype "bidirectional"))
      (node (ref "U14") (pin "12") (pinfunction "MISO_12") (pintype "bidirectional"))
    )
    (net (code "62") (name "/M6_In2") (class "Default")
      (node (ref "MD3") (pin "1") (pintype "passive"))
      (node (ref "R40") (pin "1") (pinfunction "1_1") (pintype "passive"))
      (node (ref "S12") (pin "2") (pinfunction "NO_2_2") (pintype "bidirectional"))
      (node (ref "U14") (pin "13") (pinfunction "SCK_13") (pintype "bidirectional"))
    )
    (net (code "63") (name "/M7A") (class "Default")
      (node (ref "C41") (pin "1") (pinfunction "1_1") (pintype "passive"))
      (node (ref "C49") (pin "2") (pinfunction "2_2") (pintype "passive"))
      (node (ref "J26") (pin "1") (pinfunction "POS_1") (pintype "power_in"))
      (node (ref "U12") (pin "4") (pinfunction "OUT_4") (pintype "power_in"))
    )
    (net (code "64") (name "/M7B") (class "Default")
      (node (ref "C42") (pin "1") (pinfunction "1_1") (pintype "passive"))
      (node (ref "C50") (pin "2") (pinfunction "2_2") (pintype "passive"))
      (node (ref "J26") (pin "2") (pinfunction "NEG_2") (pintype "power_in"))
      (node (ref "U13") (pin "4") (pinfunction "OUT_4") (pintype "power_in"))
    )
    (net (code "65") (name "/M7_In1") (class "Default")
      (node (ref "MD4") (pin "4") (pinfunction "4_4") (pintype "passive"))
      (node (ref "R29") (pin "1") (pinfunction "1_1") (pintype "passive"))
      (node (ref "S7") (pin "2") (pinfunction "NO_2_2") (pintype "bidirectional"))
      (node (ref "U14") (pin "15") (pinfunction "A1_15") (pintype "bidirectional"))
    )
    (net (code "66") (name "/M7_In2") (class "Default")
      (node (ref "MD4") (pin "3") (pintype "passive"))
      (node (ref "R31") (pin "1") (pinfunction "1_1") (pintype "passive"))
      (node (ref "S13") (pin "2") (pinfunction "NO_2_2") (pintype "bidirectional"))
      (node (ref "U14") (pin "14") (pinfunction "A0_14") (pintype "bidirectional"))
    )
    (net (code "67") (name "/M8A") (class "Default")
      (node (ref "C59") (pin "1") (pinfunction "1_1") (pintype "passive"))
      (node (ref "C67") (pin "2") (pinfunction "2_2") (pintype "passive"))
      (node (ref "J27") (pin "1") (pinfunction "POS_1") (pintype "power_in"))
      (node (ref "U18") (pin "4") (pinfunction "OUT_4") (pintype "power_in"))
    )
    (net (code "68") (name "/M8B") (class "Default")
      (node (ref "C60") (pin "1") (pinfunction "1_1") (pintype "passive"))
      (node (ref "C68") (pin "2") (pinfunction "2_2") (pintype "passive"))
      (node (ref "J27") (pin "2") (pinfunction "NEG_2") (pintype "power_in"))
      (node (ref "U19") (pin "4") (pinfunction "OUT_4") (pintype "power_in"))
    )
    (net (code "69") (name "/M8_In1") (class "Default")
      (node (ref "MD4") (pin "2") (pintype "passive"))
      (node (ref "R43") (pin "1") (pinfunction "1_1") (pintype "passive"))
      (node (ref "S8") (pin "2") (pinfunction "NO_2_2") (pintype "bidirectional"))
      (node (ref "U14") (pin "22") (pinfunction "A8_22") (pintype "bidirectional"))
    )
    (net (code "70") (name "/M8_In2") (class "Default")
      (node (ref "MD4") (pin "1") (pintype "passive"))
      (node (ref "R45") (pin "1") (pinfunction "1_1") (pintype "passive"))
      (node (ref "S14") (pin "2") (pinfunction "NO_2_2") (pintype "bidirectional"))
      (node (ref "U14") (pin "23") (pinfunction "A9_23") (pintype "bidirectional"))
    )
    (net (code "71") (name "/RX1_N") (class "Default")
      (node (ref "J24") (pin "6") (pinfunction "6_6") (pintype "passive"))
      (node (ref "J28") (pin "6") (pinfunction "6_6") (pintype "passive"))
    )
    (net (code "72") (name "/RX1_P") (class "Default")
      (node (ref "J24") (pin "5") (pinfunction "5_5") (pintype "passive"))
      (node (ref "J28") (pin "4") (pinfunction "4_4") (pintype "passive"))
    )
    (net (code "73") (name "/RX_8") (class "Default")
      (node (ref "R47") (pin "2") (pinfunction "2_2") (pintype "passive"))
      (node (ref "U14") (pin "34") (pinfunction "RX8_34") (pintype "bidirectional"))
    )
    (net (code "74") (name "/RX_BLDC") (class "Default")
      (node (ref "B1") (pin "1") (pintype "passive"))
      (node (ref "sw2") (pin "5") (pinfunction "COM_5") (pintype "passive"))
    )
    (net (code "75") (name "/S1") (class "Default")
      (node (ref "J2") (pin "1") (pintype "passive"))
      (node (ref "U5") (pin "14") (pinfunction "PWM13_14") (pintype "passive"))
    )
    (net (code "76") (name "/S1_Dir") (class "Default")
      (node (ref "J9") (pin "6") (pinfunction "6_6") (pintype "passive"))
      (node (ref "U14") (pin "38") (pinfunction "A14_38") (pintype "bidirectional"))
    )
    (net (code "77") (name "/S1_Stp") (class "Default")
      (node (ref "J9") (pin "4") (pinfunction "4_4") (pintype "passive"))
      (node (ref "U14") (pin "39") (pinfunction "A15_39") (pintype "bidirectional"))
    )
    (net (code "78") (name "/S2") (class "Default")
      (node (ref "J1") (pin "1") (pintype "passive"))
      (node (ref "U5") (pin "13") (pinfunction "PWM12_13") (pintype "passive"))
    )
    (net (code "79") (name "/S2_Dir") (class "Default")
      (node (ref "J14") (pin "6") (pinfunction "6_6") (pintype "passive"))
      (node (ref "U5") (pin "16") (pinfunction "PWM15_16") (pintype "passive"))
    )
    (net (code "80") (name "/S2_Stp") (class "Default")
      (node (ref "J14") (pin "4") (pinfunction "4_4") (pintype "passive"))
      (node (ref "U5") (pin "15") (pinfunction "PWM14_15") (pintype "passive"))
    )
    (net (code "81") (name "/S3") (class "Default")
      (node (ref "J6") (pin "1") (pintype "passive"))
      (node (ref "U5") (pin "12") (pinfunction "PWM11_12") (pintype "passive"))
    )
    (net (code "82") (name "/S4") (class "Default")
      (node (ref "J5") (pin "1") (pintype "passive"))
      (node (ref "U5") (pin "11") (pinfunction "PWM10_11") (pintype "passive"))
    )
    (net (code "83") (name "/S5") (class "Default")
      (node (ref "J8") (pin "1") (pintype "passive"))
      (node (ref "U5") (pin "10") (pinfunction "PWM9_10") (pintype "passive"))
    )
    (net (code "84") (name "/S6") (class "Default")
      (node (ref "J7") (pin "1") (pintype "passive"))
      (node (ref "U5") (pin "9") (pinfunction "PWM8_9") (pintype "passive"))
    )
    (net (code "85") (name "/SCL") (class "Default")
      (node (ref "U14") (pin "19") (pinfunction "A5_19") (pintype "bidirectional"))
      (node (ref "U5") (pin "52") (pinfunction "SCL_1_52") (pintype "passive"))
    )
    (net (code "86") (name "/SCL1") (class "Default")
      (node (ref "U14") (pin "16") (pinfunction "A2_16") (pintype "bidirectional"))
      (node (ref "U15") (pin "4") (pinfunction "SCL_4") (pintype "input"))
    )
    (net (code "87") (name "/SCL2") (class "Default")
      (node (ref "J22") (pin "5") (pinfunction "5_5") (pintype "passive"))
      (node (ref "U14") (pin "24") (pinfunction "A10_24") (pintype "bidirectional"))
    )
    (net (code "88") (name "/SDA") (class "Default")
      (node (ref "U14") (pin "18") (pinfunction "A4_18") (pintype "bidirectional"))
      (node (ref "U5") (pin "51") (pinfunction "SDA_1_51") (pintype "passive"))
    )
    (net (code "89") (name "/SDA1") (class "Default")
      (node (ref "U14") (pin "17") (pinfunction "A3_17") (pintype "bidirectional"))
      (node (ref "U15") (pin "5") (pinfunction "SDA_5") (pintype "bidirectional"))
    )
    (net (code "90") (name "/SDA2") (class "Default")
      (node (ref "J22") (pin "9") (pinfunction "9_9") (pintype "passive"))
      (node (ref "U14") (pin "25") (pinfunction "A11_25") (pintype "bidirectional"))
    )
    (net (code "91") (name "/TX1_N") (class "Default")
      (node (ref "J24") (pin "1") (pinfunction "1_1") (pintype "passive"))
      (node (ref "J28") (pin "3") (pinfunction "3_3") (pintype "passive"))
    )
    (net (code "92") (name "/TX1_P") (class "Default")
      (node (ref "J24") (pin "2") (pinfunction "2_2") (pintype "passive"))
      (node (ref "J28") (pin "1") (pinfunction "1_1") (pintype "passive"))
    )
    (net (code "93") (name "/TX_8") (class "Default")
      (node (ref "R38") (pin "2") (pinfunction "2_2") (pintype "passive"))
      (node (ref "U14") (pin "35") (pinfunction "TX8_35") (pintype "bidirectional"))
    )
    (net (code "94") (name "/TX_BLDC") (class "Default")
      (node (ref "B1") (pin "2") (pintype "passive"))
      (node (ref "sw2") (pin "2") (pinfunction "COM_2") (pintype "passive"))
    )
    (net (code "95") (name "3V3") (class "Default")
      (node (ref "Buck3") (pin "OUT+") (pinfunction "OUT+_OUT+") (pintype "power_in"))
      (node (ref "R15") (pin "1") (pinfunction "1_1") (pintype "passive"))
      (node (ref "R17") (pin "1") (pinfunction "1_1") (pintype "passive"))
      (node (ref "R19") (pin "1") (pinfunction "1_1") (pintype "passive"))
      (node (ref "R21") (pin "1") (pinfunction "1_1") (pintype "passive"))
      (node (ref "R26") (pin "1") (pinfunction "1_1") (pintype "passive"))
      (node (ref "R28") (pin "1") (pinfunction "1_1") (pintype "passive"))
      (node (ref "R3") (pin "1") (pinfunction "1_1") (pintype "passive"))
      (node (ref "R30") (pin "1") (pinfunction "1_1") (pintype "passive"))
      (node (ref "R32") (pin "1") (pinfunction "1_1") (pintype "passive"))
      (node (ref "R39") (pin "1") (pinfunction "1_1") (pintype "passive"))
      (node (ref "R41") (pin "1") (pinfunction "1_1") (pintype "passive"))
      (node (ref "R44") (pin "1") (pinfunction "1_1") (pintype "passive"))
      (node (ref "R46") (pin "1") (pinfunction "1_1") (pintype "passive"))
      (node (ref "R5") (pin "1") (pinfunction "1_1") (pintype "passive"))
      (node (ref "R7") (pin "1") (pinfunction "1_1") (pintype "passive"))
      (node (ref "R9") (pin "1") (pinfunction "1_1") (pintype "passive"))
      (node (ref "S1") (pin "4") (pinfunction "COM_2_4") (pintype "input"))
      (node (ref "S10") (pin "4") (pinfunction "COM_2_4") (pintype "input"))
      (node (ref "S11") (pin "4") (pinfunction "COM_2_4") (pintype "input"))
      (node (ref "S12") (pin "4") (pinfunction "COM_2_4") (pintype "input"))
      (node (ref "S13") (pin "4") (pinfunction "COM_2_4") (pintype "input"))
      (node (ref "S14") (pin "4") (pinfunction "COM_2_4") (pintype "input"))
      (node (ref "S15") (pin "4") (pinfunction "COM_2_4") (pintype "input"))
      (node (ref "S16") (pin "4") (pinfunction "COM_2_4") (pintype "input"))
      (node (ref "S2") (pin "4") (pinfunction "COM_2_4") (pintype "input"))
      (node (ref "S3") (pin "4") (pinfunction "COM_2_4") (pintype "input"))
      (node (ref "S4") (pin "4") (pinfunction "COM_2_4") (pintype "input"))
      (node (ref "S5") (pin "4") (pinfunction "COM_2_4") (pintype "input"))
      (node (ref "S6") (pin "4") (pinfunction "COM_2_4") (pintype "input"))
      (node (ref "S7") (pin "4") (pinfunction "COM_2_4") (pintype "input"))
      (node (ref "S8") (pin "4") (pinfunction "COM_2_4") (pintype "input"))
      (node (ref "S9") (pin "4") (pinfunction "COM_2_4") (pintype "input"))
    )
    (net (code "96") (name "5V") (class "Default")
      (node (ref "J23") (pin "01") (pinfunction "VCC_01") (pintype "power_in"))
      (node (ref "U14") (pin "5V") (pinfunction "5V_5V") (pintype "power_in"))
    )
    (net (code "97") (name "GND") (class "Default")
      (node (ref "*5") (pin "4") (pinfunction "GND_4") (pintype "power_in"))
      (node (ref "*5") (pin "9") (pinfunction "GND_9") (pintype "power_in"))
      (node (ref "B1") (pin "3") (pintype "passive"))
      (node (ref "Buck1") (pin "IN-") (pinfunction "IN-_IN-") (pintype "power_in"))
      (node (ref "Buck1") (pin "OUT-") (pinfunction "OUT-_OUT-") (pintype "power_in"))
      (node (ref "Buck2") (pin "IN-") (pinfunction "IN-_IN-") (pintype "power_in"))
      (node (ref "Buck2") (pin "OUT-") (pinfunction "OUT-_OUT-") (pintype "power_in"))
      (node (ref "Buck3") (pin "IN-") (pinfunction "IN-_IN-") (pintype "power_in"))
      (node (ref "Buck3") (pin "OUT-") (pinfunction "OUT-_OUT-") (pintype "power_in"))
      (node (ref "Buck4") (pin "IN-") (pinfunction "IN-_IN-") (pintype "power_in"))
      (node (ref "Buck4") (pin "OUT-") (pinfunction "OUT-_OUT-") (pintype "power_in"))
      (node (ref "C1") (pin "N") (pinfunction "N_N") (pintype "passive"))
      (node (ref "C10") (pin "2") (pinfunction "2_2") (pintype "passive"))
      (node (ref "C11") (pin "1") (pinfunction "1_1") (pintype "passive"))
      (node (ref "C12") (pin "1") (pinfunction "1_1") (pintype "passive"))
      (node (ref "C13") (pin "1") (pinfunction "1_1") (pintype "passive"))
      (node (ref "C14") (pin "1") (pinfunction "1_1") (pintype "passive"))
      (node (ref "C15") (pin "2") (pinfunction "2_2") (pintype "passive"))
      (node (ref "C16") (pin "2") (pinfunction "2_2") (pintype "passive"))
      (node (ref "C17") (pin "2") (pinfunction "2_2") (pintype "passive"))
      (node (ref "C18") (pin "2") (pinfunction "2_2") (pintype "passive"))
      (node (ref "C19") (pin "N") (pinfunction "N_N") (pintype "passive"))
      (node (ref "C2") (pin "N") (pinfunction "N_N") (pintype "passive"))
      (node (ref "C20") (pin "N") (pinfunction "N_N") (pintype "passive"))
      (node (ref "C25") (pin "2") (pinfunction "2_2") (pintype "passive"))
      (node (ref "C26") (pin "2") (pinfunction "2_2") (pintype "passive"))
      (node (ref "C27") (pin "2") (pinfunction "2_2") (pintype "passive"))
      (node (ref "C28") (pin "2") (pinfunction "2_2") (pintype "passive"))
      (node (ref "C29") (pin "1") (pinfunction "1_1") (pintype "passive"))
      (node (ref "C30") (pin "1") (pinfunction "1_1") (pintype "passive"))
      (node (ref "C31") (pin "1") (pinfunction "1_1") (pintype "passive"))
      (node (ref "C32") (pin "1") (pinfunction "1_1") (pintype "passive"))
      (node (ref "C33") (pin "2") (pinfunction "2_2") (pintype "passive"))
      (node (ref "C34") (pin "2") (pinfunction "2_2") (pintype "passive"))
      (node (ref "C35") (pin "2") (pinfunction "2_2") (pintype "passive"))
      (node (ref "C36") (pin "2") (pinfunction "2_2") (pintype "passive"))
      (node (ref "C37") (pin "N") (pinfunction "N_N") (pintype "passive"))
      (node (ref "C38") (pin "N") (pinfunction "N_N") (pintype "passive"))
      (node (ref "C43") (pin "2") (pinfunction "2_2") (pintype "passive"))
      (node (ref "C44") (pin "2") (pinfunction "2_2") (pintype "passive"))
      (node (ref "C45") (pin "2") (pinfunction "2_2") (pintype "passive"))
      (node (ref "C46") (pin "2") (pinfunction "2_2") (pintype "passive"))
      (node (ref "C47") (pin "1") (pinfunction "1_1") (pintype "passive"))
      (node (ref "C48") (pin "1") (pinfunction "1_1") (pintype "passive"))
      (node (ref "C49") (pin "1") (pinfunction "1_1") (pintype "passive"))
      (node (ref "C50") (pin "1") (pinfunction "1_1") (pintype "passive"))
      (node (ref "C51") (pin "2") (pinfunction "2_2") (pintype "passive"))
      (node (ref "C52") (pin "2") (pinfunction "2_2") (pintype "passive"))
      (node (ref "C53") (pin "2") (pinfunction "2_2") (pintype "passive"))
      (node (ref "C54") (pin "2") (pinfunction "2_2") (pintype "passive"))
      (node (ref "C55") (pin "N") (pinfunction "N_N") (pintype "passive"))
      (node (ref "C56") (pin "N") (pinfunction "N_N") (pintype "passive"))
      (node (ref "C61") (pin "2") (pinfunction "2_2") (pintype "passive"))
      (node (ref "C62") (pin "2") (pinfunction "2_2") (pintype "passive"))
      (node (ref "C63") (pin "1") (pinfunction "1_1") (pintype "passive"))
      (node (ref "C64") (pin "1") (pinfunction "1_1") (pintype "passive"))
      (node (ref "C65") (pin "2") (pinfunction "2_2") (pintype "passive"))
      (node (ref "C66") (pin "2") (pinfunction "2_2") (pintype "passive"))
      (node (ref "C67") (pin "1") (pinfunction "1_1") (pintype "passive"))
      (node (ref "C68") (pin "1") (pinfunction "1_1") (pintype "passive"))
      (node (ref "C69") (pin "2") (pinfunction "2_2") (pintype "passive"))
      (node (ref "C7") (pin "2") (pinfunction "2_2") (pintype "passive"))
      (node (ref "C70") (pin "2") (pinfunction "2_2") (pintype "passive"))
      (node (ref "C71") (pin "2") (pinfunction "2_2") (pintype "passive"))
      (node (ref "C72") (pin "2") (pinfunction "2_2") (pintype "passive"))
      (node (ref "C73") (pin "2") (pinfunction "2_2") (pintype "passive"))
      (node (ref "C8") (pin "2") (pinfunction "2_2") (pintype "passive"))
      (node (ref "C9") (pin "2") (pinfunction "2_2") (pintype "passive"))
      (node (ref "E1") (pin "2") (pintype "passive"))
      (node (ref "E2") (pin "2") (pintype "passive"))
      (node (ref "E3") (pin "2") (pintype "passive"))
      (node (ref "E4") (pin "2") (pintype "passive"))
      (node (ref "E5") (pin "2") (pintype "passive"))
      (node (ref "E6") (pin "2") (pintype "passive"))
      (node (ref "J1") (pin "3") (pintype "passive"))
      (node (ref "J10") (pin "2") (pinfunction "NEG_2") (pintype "power_in"))
      (node (ref "J11") (pin "2") (pinfunction "NEG_2") (pintype "power_in"))
      (node (ref "J14") (pin "1") (pinfunction "1_1") (pintype "passive"))
      (node (ref "J14") (pin "3") (pinfunction "3_3") (pintype "passive"))
      (node (ref "J14") (pin "5") (pinfunction "5_5") (pintype "passive"))
      (node (ref "J14") (pin "7") (pinfunction "7_7") (pintype "passive"))
      (node (ref "J15") (pin "2") (pinfunction "NEG_2") (pintype "power_in"))
      (node (ref "J16") (pin "2") (pinfunction "NEG_2") (pintype "power_in"))
      (node (ref "J17") (pin "2") (pinfunction "NEG_2") (pintype "power_in"))
      (node (ref "J18") (pin "2") (pinfunction "NEG_2") (pintype "power_in"))
      (node (ref "J19") (pin "2") (pinfunction "NEG_2") (pintype "power_in"))
      (node (ref "J2") (pin "3") (pintype "passive"))
      (node (ref "J22") (pin "6") (pinfunction "6_6") (pintype "passive"))
      (node (ref "J23") (pin "04") (pinfunction "GND_04") (pintype "power_in"))
      (node (ref "J24") (pin "4") (pinfunction "4_4") (pintype "passive"))
      (node (ref "J28") (pin "8") (pinfunction "8_8") (pintype "passive"))
      (node (ref "J28") (pin "SH1") (pinfunction "SHIELD_SH1") (pintype "passive"))
      (node (ref "J3") (pin "2") (pinfunction "NEG_2") (pintype "power_in"))
      (node (ref "J30") (pin "12") (pinfunction "12_12") (pintype "passive"))
      (node (ref "J5") (pin "3") (pintype "passive"))
      (node (ref "J6") (pin "3") (pintype "passive"))
      (node (ref "J7") (pin "3") (pintype "passive"))
      (node (ref "J8") (pin "3") (pintype "passive"))
      (node (ref "J9") (pin "1") (pinfunction "1_1") (pintype "passive"))
      (node (ref "J9") (pin "3") (pinfunction "3_3") (pintype "passive"))
      (node (ref "J9") (pin "5") (pinfunction "5_5") (pintype "passive"))
      (node (ref "J9") (pin "7") (pinfunction "7_7") (pintype "passive"))
      (node (ref "L1") (pin "K") (pinfunction "C_K") (pintype "passive"))
      (node (ref "L2") (pin "K") (pinfunction "C_K") (pintype "passive"))
      (node (ref "L3") (pin "K") (pinfunction "C_K") (pintype "passive"))
      (node (ref "L4") (pin "K") (pinfunction "C_K") (pintype "passive"))
      (node (ref "L5") (pin "K") (pinfunction "C_K") (pintype "passive"))
      (node (ref "LED1") (pin "K") (pinfunction "C_K") (pintype "passive"))
      (node (ref "LS1") (pin "2") (pinfunction "2_2") (pintype "passive"))
      (node (ref "LS2") (pin "2") (pinfunction "2_2") (pintype "passive"))
      (node (ref "LS3") (pin "2") (pinfunction "2_2") (pintype "passive"))
      (node (ref "LS4") (pin "2") (pinfunction "2_2") (pintype "passive"))
      (node (ref "MD1") (pin "5") (pinfunction "5_5") (pintype "passive"))
      (node (ref "MD1") (pin "6") (pinfunction "6_6") (pintype "passive"))
      (node (ref "MD2") (pin "5") (pinfunction "5_5") (pintype "passive"))
      (node (ref "MD2") (pin "6") (pinfunction "6_6") (pintype "passive"))
      (node (ref "MD3") (pin "5") (pinfunction "5_5") (pintype "passive"))
      (node (ref "MD3") (pin "6") (pinfunction "6_6") (pintype "passive"))
      (node (ref "MD4") (pin "5") (pinfunction "5_5") (pintype "passive"))
      (node (ref "MD4") (pin "6") (pinfunction "6_6") (pintype "passive"))
      (node (ref "R10") (pin "1") (pinfunction "1_1") (pintype "passive"))
      (node (ref "R11") (pin "1") (pinfunction "1_1") (pintype "passive"))
      (node (ref "R12") (pin "1") (pinfunction "1_1") (pintype "passive"))
      (node (ref "R13") (pin "1") (pinfunction "1_1") (pintype "passive"))
      (node (ref "R22") (pin "1") (pinfunction "1_1") (pintype "passive"))
      (node (ref "R23") (pin "1") (pinfunction "1_1") (pintype "passive"))
      (node (ref "R24") (pin "1") (pinfunction "1_1") (pintype "passive"))
      (node (ref "R25") (pin "1") (pinfunction "1_1") (pintype "passive"))
      (node (ref "R34") (pin "1") (pinfunction "1_1") (pintype "passive"))
      (node (ref "R35") (pin "1") (pinfunction "1_1") (pintype "passive"))
      (node (ref "R36") (pin "1") (pinfunction "1_1") (pintype "passive"))
      (node (ref "R37") (pin "1") (pinfunction "1_1") (pintype "passive"))
      (node (ref "R48") (pin "1") (pinfunction "1_1") (pintype "passive"))
      (node (ref "R49") (pin "1") (pinfunction "1_1") (pintype "passive"))
      (node (ref "R50") (pin "1") (pinfunction "1_1") (pintype "passive"))
      (node (ref "R51") (pin "1") (pinfunction "1_1") (pintype "passive"))
      (node (ref "U1") (pin "1") (pinfunction "GND_1") (pintype "power_in"))
      (node (ref "U10") (pin "1") (pinfunction "GND_1") (pintype "power_in"))
      (node (ref "U11") (pin "1") (pinfunction "GND_1") (pintype "power_in"))
      (node (ref "U12") (pin "1") (pinfunction "GND_1") (pintype "power_in"))
      (node (ref "U13") (pin "1") (pinfunction "GND_1") (pintype "power_in"))
      (node (ref "U14") (pin "GND1") (pinfunction "GND_GND1") (pintype "power_in"))
      (node (ref "U14") (pin "GND2") (pinfunction "GND_GND2") (pintype "power_in"))
      (node (ref "U14") (pin "GND3") (pinfunction "GND_GND3") (pintype "power_in"))
      (node (ref "U14") (pin "USB_GND1") (pinfunction "USB_GND_USB_GND1") (pintype "power_in"))
      (node (ref "U14") (pin "USB_GND2") (pinfunction "USB_GND_USB_GND2") (pintype "power_in"))
      (node (ref "U15") (pin "3") (pinfunction "GND_3") (pintype "power_in"))
      (node (ref "U16") (pin "1") (pinfunction "GND_1") (pintype "power_in"))
      (node (ref "U17") (pin "1") (pinfunction "GND_1") (pintype "power_in"))
      (node (ref "U18") (pin "1") (pinfunction "GND_1") (pintype "power_in"))
      (node (ref "U19") (pin "1") (pinfunction "GND_1") (pintype "power_in"))
      (node (ref "U2") (pin "1") (pinfunction "GND_1") (pintype "power_in"))
      (node (ref "U3") (pin "1") (pinfunction "GND_1") (pintype "power_in"))
      (node (ref "U4") (pin "1") (pinfunction "GND_1") (pintype "power_in"))
      (node (ref "U5") (pin "54") (pinfunction "GND_1_54") (pintype "passive"))
      (node (ref "U6") (pin "1") (pinfunction "GND_1") (pintype "power_in"))
      (node (ref "U7") (pin "1") (pinfunction "GND_1") (pintype "power_in"))
      (node (ref "U8") (pin "1") (pinfunction "GND_1") (pintype "power_in"))
      (node (ref "U9") (pin "1") (pinfunction "GND_1") (pintype "power_in"))
    )
    (net (code "98") (name "Net-(*1-Pad2)") (class "Default")
      (node (ref "*1") (pin "2") (pinfunction "2_2") (pintype "passive"))
      (node (ref "L2") (pin "A") (pinfunction "A_A") (pintype "passive"))
    )
    (net (code "99") (name "Net-(*2-Pad2)") (class "Default")
      (node (ref "*2") (pin "2") (pinfunction "2_2") (pintype "passive"))
      (node (ref "L3") (pin "A") (pinfunction "A_A") (pintype "passive"))
    )
    (net (code "100") (name "Net-(*3-Pad2)") (class "Default")
      (node (ref "*3") (pin "2") (pinfunction "2_2") (pintype "passive"))
      (node (ref "L4") (pin "A") (pinfunction "A_A") (pintype "passive"))
    )
    (net (code "101") (name "Net-(*4-Pad2)") (class "Default")
      (node (ref "*4") (pin "2") (pinfunction "2_2") (pintype "passive"))
      (node (ref "L5") (pin "A") (pinfunction "A_A") (pintype "passive"))
    )
    (net (code "102") (name "Net-(C73-Pad1)") (class "Default")
      (node (ref "C73") (pin "1") (pinfunction "1_1") (pintype "passive"))
      (node (ref "J28") (pin "2") (pinfunction "2_2") (pintype "passive"))
      (node (ref "J28") (pin "5") (pinfunction "5_5") (pintype "passive"))
    )
    (net (code "103") (name "Net-(L1-PadA)") (class "Default")
      (node (ref "L1") (pin "A") (pinfunction "A_A") (pintype "passive"))
      (node (ref "R1") (pin "1") (pinfunction "1_1") (pintype "passive"))
    )
    (net (code "104") (name "Net-(LED1-PadA)") (class "Default")
      (node (ref "LED1") (pin "A") (pinfunction "A_A") (pintype "passive"))
      (node (ref "sw2") (pin "3") (pinfunction "C2_3") (pintype "passive"))
    )
    (net (code "105") (name "Net-(R38-Pad1)") (class "Default")
      (node (ref "R38") (pin "1") (pinfunction "1_1") (pintype "passive"))
      (node (ref "sw2") (pin "6") (pinfunction "C1_6") (pintype "passive"))
    )
    (net (code "106") (name "Net-(R47-Pad1)") (class "Default")
      (node (ref "R47") (pin "1") (pinfunction "1_1") (pintype "passive"))
      (node (ref "sw2") (pin "1") (pinfunction "C1_1") (pintype "passive"))
    )
    (net (code "107") (name "Net-(U1-IN)") (class "Default")
      (node (ref "R2") (pin "2") (pinfunction "2_2") (pintype "passive"))
      (node (ref "U1") (pin "2") (pinfunction "IN_2") (pintype "input"))
    )
    (net (code "108") (name "Net-(U1-INH)") (class "Default")
      (node (ref "R3") (pin "2") (pinfunction "2_2") (pintype "passive"))
      (node (ref "U1") (pin "3") (pinfunction "INH_3") (pintype "input"))
    )
    (net (code "109") (name "Net-(U1-SR)") (class "Default")
      (node (ref "C15") (pin "1") (pinfunction "1_1") (pintype "passive"))
      (node (ref "R10") (pin "2") (pinfunction "2_2") (pintype "passive"))
      (node (ref "U1") (pin "5") (pinfunction "SR_5") (pintype "input"))
    )
    (net (code "110") (name "Net-(U2-IN)") (class "Default")
      (node (ref "R4") (pin "2") (pinfunction "2_2") (pintype "passive"))
      (node (ref "U2") (pin "2") (pinfunction "IN_2") (pintype "input"))
    )
    (net (code "111") (name "Net-(U2-INH)") (class "Default")
      (node (ref "R5") (pin "2") (pinfunction "2_2") (pintype "passive"))
      (node (ref "U2") (pin "3") (pinfunction "INH_3") (pintype "input"))
    )
    (net (code "112") (name "Net-(U2-SR)") (class "Default")
      (node (ref "C16") (pin "1") (pinfunction "1_1") (pintype "passive"))
      (node (ref "R11") (pin "2") (pinfunction "2_2") (pintype "passive"))
      (node (ref "U2") (pin "5") (pinfunction "SR_5") (pintype "input"))
    )
    (net (code "113") (name "Net-(U3-IN)") (class "Default")
      (node (ref "R6") (pin "2") (pinfunction "2_2") (pintype "passive"))
      (node (ref "U3") (pin "2") (pinfunction "IN_2") (pintype "input"))
    )
    (net (code "114") (name "Net-(U3-INH)") (class "Default")
      (node (ref "R7") (pin "2") (pinfunction "2_2") (pintype "passive"))
      (node (ref "U3") (pin "3") (pinfunction "INH_3") (pintype "input"))
    )
    (net (code "115") (name "Net-(U3-SR)") (class "Default")
      (node (ref "C17") (pin "1") (pinfunction "1_1") (pintype "passive"))
      (node (ref "R12") (pin "2") (pinfunction "2_2") (pintype "passive"))
      (node (ref "U3") (pin "5") (pinfunction "SR_5") (pintype "input"))
    )
    (net (code "116") (name "Net-(U4-IN)") (class "Default")
      (node (ref "R8") (pin "2") (pinfunction "2_2") (pintype "passive"))
      (node (ref "U4") (pin "2") (pinfunction "IN_2") (pintype "input"))
    )
    (net (code "117") (name "Net-(U4-INH)") (class "Default")
      (node (ref "R9") (pin "2") (pinfunction "2_2") (pintype "passive"))
      (node (ref "U4") (pin "3") (pinfunction "INH_3") (pintype "input"))
    )
    (net (code "118") (name "Net-(U4-SR)") (class "Default")
      (node (ref "C18") (pin "1") (pinfunction "1_1") (pintype "passive"))
      (node (ref "R13") (pin "2") (pinfunction "2_2") (pintype "passive"))
      (node (ref "U4") (pin "5") (pinfunction "SR_5") (pintype "input"))
    )
    (net (code "119") (name "Net-(U6-IN)") (class "Default")
      (node (ref "R14") (pin "2") (pinfunction "2_2") (pintype "passive"))
      (node (ref "U6") (pin "2") (pinfunction "IN_2") (pintype "input"))
    )
    (net (code "120") (name "Net-(U6-INH)") (class "Default")
      (node (ref "R15") (pin "2") (pinfunction "2_2") (pintype "passive"))
      (node (ref "U6") (pin "3") (pinfunction "INH_3") (pintype "input"))
    )
    (net (code "121") (name "Net-(U6-SR)") (class "Default")
      (node (ref "C33") (pin "1") (pinfunction "1_1") (pintype "passive"))
      (node (ref "R22") (pin "2") (pinfunction "2_2") (pintype "passive"))
      (node (ref "U6") (pin "5") (pinfunction "SR_5") (pintype "input"))
    )
    (net (code "122") (name "Net-(U7-IN)") (class "Default")
      (node (ref "R16") (pin "2") (pinfunction "2_2") (pintype "passive"))
      (node (ref "U7") (pin "2") (pinfunction "IN_2") (pintype "input"))
    )
    (net (code "123") (name "Net-(U7-INH)") (class "Default")
      (node (ref "R17") (pin "2") (pinfunction "2_2") (pintype "passive"))
      (node (ref "U7") (pin "3") (pinfunction "INH_3") (pintype "input"))
    )
    (net (code "124") (name "Net-(U7-SR)") (class "Default")
      (node (ref "C34") (pin "1") (pinfunction "1_1") (pintype "passive"))
      (node (ref "R23") (pin "2") (pinfunction "2_2") (pintype "passive"))
      (node (ref "U7") (pin "5") (pinfunction "SR_5") (pintype "input"))
    )
    (net (code "125") (name "Net-(U8-IN)") (class "Default")
      (node (ref "R18") (pin "2") (pinfunction "2_2") (pintype "passive"))
      (node (ref "U8") (pin "2") (pinfunction "IN_2") (pintype "input"))
    )
    (net (code "126") (name "Net-(U8-INH)") (class "Default")
      (node (ref "R19") (pin "2") (pinfunction "2_2") (pintype "passive"))
      (node (ref "U8") (pin "3") (pinfunction "INH_3") (pintype "input"))
    )
    (net (code "127") (name "Net-(U8-SR)") (class "Default")
      (node (ref "C35") (pin "1") (pinfunction "1_1") (pintype "passive"))
      (node (ref "R24") (pin "2") (pinfunction "2_2") (pintype "passive"))
      (node (ref "U8") (pin "5") (pinfunction "SR_5") (pintype "input"))
    )
    (net (code "128") (name "Net-(U9-IN)") (class "Default")
      (node (ref "R20") (pin "2") (pinfunction "2_2") (pintype "passive"))
      (node (ref "U9") (pin "2") (pinfunction "IN_2") (pintype "input"))
    )
    (net (code "129") (name "Net-(U9-INH)") (class "Default")
      (node (ref "R21") (pin "2") (pinfunction "2_2") (pintype "passive"))
      (node (ref "U9") (pin "3") (pinfunction "INH_3") (pintype "input"))
    )
    (net (code "130") (name "Net-(U9-SR)") (class "Default")
      (node (ref "C36") (pin "1") (pinfunction "1_1") (pintype "passive"))
      (node (ref "R25") (pin "2") (pinfunction "2_2") (pintype "passive"))
      (node (ref "U9") (pin "5") (pinfunction "SR_5") (pintype "input"))
    )
    (net (code "131") (name "Net-(U10-IN)") (class "Default")
      (node (ref "R33") (pin "2") (pinfunction "2_2") (pintype "passive"))
      (node (ref "U10") (pin "2") (pinfunction "IN_2") (pintype "input"))
    )
    (net (code "132") (name "Net-(U10-INH)") (class "Default")
      (node (ref "R26") (pin "2") (pinfunction "2_2") (pintype "passive"))
      (node (ref "U10") (pin "3") (pinfunction "INH_3") (pintype "input"))
    )
    (net (code "133") (name "Net-(U10-SR)") (class "Default")
      (node (ref "C51") (pin "1") (pinfunction "1_1") (pintype "passive"))
      (node (ref "R34") (pin "2") (pinfunction "2_2") (pintype "passive"))
      (node (ref "U10") (pin "5") (pinfunction "SR_5") (pintype "input"))
    )
    (net (code "134") (name "Net-(U11-IN)") (class "Default")
      (node (ref "R27") (pin "2") (pinfunction "2_2") (pintype "passive"))
      (node (ref "U11") (pin "2") (pinfunction "IN_2") (pintype "input"))
    )
    (net (code "135") (name "Net-(U11-INH)") (class "Default")
      (node (ref "R28") (pin "2") (pinfunction "2_2") (pintype "passive"))
      (node (ref "U11") (pin "3") (pinfunction "INH_3") (pintype "input"))
    )
    (net (code "136") (name "Net-(U11-SR)") (class "Default")
      (node (ref "C52") (pin "1") (pinfunction "1_1") (pintype "passive"))
      (node (ref "R35") (pin "2") (pinfunction "2_2") (pintype "passive"))
      (node (ref "U11") (pin "5") (pinfunction "SR_5") (pintype "input"))
    )
    (net (code "137") (name "Net-(U12-IN)") (class "Default")
      (node (ref "R29") (pin "2") (pinfunction "2_2") (pintype "passive"))
      (node (ref "U12") (pin "2") (pinfunction "IN_2") (pintype "input"))
    )
    (net (code "138") (name "Net-(U12-INH)") (class "Default")
      (node (ref "R30") (pin "2") (pinfunction "2_2") (pintype "passive"))
      (node (ref "U12") (pin "3") (pinfunction "INH_3") (pintype "input"))
    )
    (net (code "139") (name "Net-(U12-SR)") (class "Default")
      (node (ref "C53") (pin "1") (pinfunction "1_1") (pintype "passive"))
      (node (ref "R36") (pin "2") (pinfunction "2_2") (pintype "passive"))
      (node (ref "U12") (pin "5") (pinfunction "SR_5") (pintype "input"))
    )
    (net (code "140") (name "Net-(U13-IN)") (class "Default")
      (node (ref "R31") (pin "2") (pinfunction "2_2") (pintype "passive"))
      (node (ref "U13") (pin "2") (pinfunction "IN_2") (pintype "input"))
    )
    (net (code "141") (name "Net-(U13-INH)") (class "Default")
      (node (ref "R32") (pin "2") (pinfunction "2_2") (pintype "passive"))
      (node (ref "U13") (pin "3") (pinfunction "INH_3") (pintype "input"))
    )
    (net (code "142") (name "Net-(U13-SR)") (class "Default")
      (node (ref "C54") (pin "1") (pinfunction "1_1") (pintype "passive"))
      (node (ref "R37") (pin "2") (pinfunction "2_2") (pintype "passive"))
      (node (ref "U13") (pin "5") (pinfunction "SR_5") (pintype "input"))
    )
    (net (code "143") (name "Net-(U16-IN)") (class "Default")
      (node (ref "R42") (pin "2") (pinfunction "2_2") (pintype "passive"))
      (node (ref "U16") (pin "2") (pinfunction "IN_2") (pintype "input"))
    )
    (net (code "144") (name "Net-(U16-INH)") (class "Default")
      (node (ref "R39") (pin "2") (pinfunction "2_2") (pintype "passive"))
      (node (ref "U16") (pin "3") (pinfunction "INH_3") (pintype "input"))
    )
    (net (code "145") (name "Net-(U16-SR)") (class "Default")
      (node (ref "C69") (pin "1") (pinfunction "1_1") (pintype "passive"))
      (node (ref "R48") (pin "2") (pinfunction "2_2") (pintype "passive"))
      (node (ref "U16") (pin "5") (pinfunction "SR_5") (pintype "input"))
    )
    (net (code "146") (name "Net-(U17-IN)") (class "Default")
      (node (ref "R40") (pin "2") (pinfunction "2_2") (pintype "passive"))
      (node (ref "U17") (pin "2") (pinfunction "IN_2") (pintype "input"))
    )
    (net (code "147") (name "Net-(U17-INH)") (class "Default")
      (node (ref "R41") (pin "2") (pinfunction "2_2") (pintype "passive"))
      (node (ref "U17") (pin "3") (pinfunction "INH_3") (pintype "input"))
    )
    (net (code "148") (name "Net-(U17-SR)") (class "Default")
      (node (ref "C70") (pin "1") (pinfunction "1_1") (pintype "passive"))
      (node (ref "R49") (pin "2") (pinfunction "2_2") (pintype "passive"))
      (node (ref "U17") (pin "5") (pinfunction "SR_5") (pintype "input"))
    )
    (net (code "149") (name "Net-(U18-IN)") (class "Default")
      (node (ref "R43") (pin "2") (pinfunction "2_2") (pintype "passive"))
      (node (ref "U18") (pin "2") (pinfunction "IN_2") (pintype "input"))
    )
    (net (code "150") (name "Net-(U18-INH)") (class "Default")
      (node (ref "R44") (pin "2") (pinfunction "2_2") (pintype "passive"))
      (node (ref "U18") (pin "3") (pinfunction "INH_3") (pintype "input"))
    )
    (net (code "151") (name "Net-(U18-SR)") (class "Default")
      (node (ref "C71") (pin "1") (pinfunction "1_1") (pintype "passive"))
      (node (ref "R50") (pin "2") (pinfunction "2_2") (pintype "passive"))
      (node (ref "U18") (pin "5") (pinfunction "SR_5") (pintype "input"))
    )
    (net (code "152") (name "Net-(U19-IN)") (class "Default")
      (node (ref "R45") (pin "2") (pinfunction "2_2") (pintype "passive"))
      (node (ref "U19") (pin "2") (pinfunction "IN_2") (pintype "input"))
    )
    (net (code "153") (name "Net-(U19-INH)") (class "Default")
      (node (ref "R46") (pin "2") (pinfunction "2_2") (pintype "passive"))
      (node (ref "U19") (pin "3") (pinfunction "INH_3") (pintype "input"))
    )
    (net (code "154") (name "Net-(U19-SR)") (class "Default")
      (node (ref "C72") (pin "1") (pinfunction "1_1") (pintype "passive"))
      (node (ref "R51") (pin "2") (pinfunction "2_2") (pintype "passive"))
      (node (ref "U19") (pin "5") (pinfunction "SR_5") (pintype "input"))
    )
    (net (code "155") (name "VCC") (class "Default")
      (node (ref "Buck1") (pin "IN+") (pinfunction "IN+_IN+") (pintype "power_in"))
      (node (ref "Buck2") (pin "IN+") (pinfunction "IN+_IN+") (pintype "power_in"))
      (node (ref "Buck3") (pin "IN+") (pinfunction "IN+_IN+") (pintype "power_in"))
      (node (ref "Buck4") (pin "IN+") (pinfunction "IN+_IN+") (pintype "power_in"))
      (node (ref "F1") (pin "1_1") (pinfunction "1_1_1") (pintype "passive"))
      (node (ref "F1") (pin "1_2") (pinfunction "1_1_2") (pintype "passive"))
      (node (ref "F2") (pin "1_1") (pinfunction "1_1_1") (pintype "passive"))
      (node (ref "F2") (pin "1_2") (pinfunction "1_1_2") (pintype "passive"))
      (node (ref "F3") (pin "1_1") (pinfunction "1_1_1") (pintype "passive"))
      (node (ref "F3") (pin "1_2") (pinfunction "1_1_2") (pintype "passive"))
      (node (ref "F4") (pin "1_1") (pinfunction "1_1_1") (pintype "passive"))
      (node (ref "F4") (pin "1_2") (pinfunction "1_1_2") (pintype "passive"))
      (node (ref "J10") (pin "1") (pinfunction "POS_1") (pintype "power_in"))
      (node (ref "J15") (pin "1") (pinfunction "POS_1") (pintype "power_in"))
      (node (ref "J19") (pin "1") (pinfunction "POS_1") (pintype "power_in"))
      (node (ref "J4") (pin "1") (pinfunction "POS_1") (pintype "power_in"))
    )
    (net (code "156") (name "VCC_M1M2") (class "Default")
      (node (ref "*1") (pin "1") (pinfunction "1_1") (pintype "passive"))
      (node (ref "C1") (pin "P") (pinfunction "P_P") (pintype "passive"))
      (node (ref "C19") (pin "P") (pinfunction "P_P") (pintype "passive"))
      (node (ref "C21") (pin "2") (pinfunction "2_2") (pintype "passive"))
      (node (ref "C22") (pin "2") (pinfunction "2_2") (pintype "passive"))
      (node (ref "C25") (pin "1") (pinfunction "1_1") (pintype "passive"))
      (node (ref "C26") (pin "1") (pinfunction "1_1") (pintype "passive"))
      (node (ref "C3") (pin "2") (pinfunction "2_2") (pintype "passive"))
      (node (ref "C4") (pin "2") (pinfunction "2_2") (pintype "passive"))
      (node (ref "C7") (pin "1") (pinfunction "1_1") (pintype "passive"))
      (node (ref "C8") (pin "1") (pinfunction "1_1") (pintype "passive"))
      (node (ref "F1") (pin "2_1") (pinfunction "2_2_1") (pintype "passive"))
      (node (ref "F1") (pin "2_2") (pinfunction "2_2_2") (pintype "passive"))
      (node (ref "U1") (pin "7") (pinfunction "VS_7") (pintype "power_in"))
      (node (ref "U2") (pin "7") (pinfunction "VS_7") (pintype "power_in"))
      (node (ref "U6") (pin "7") (pinfunction "VS_7") (pintype "power_in"))
      (node (ref "U7") (pin "7") (pinfunction "VS_7") (pintype "power_in"))
    )
    (net (code "157") (name "VCC_M3M4") (class "Default")
      (node (ref "*2") (pin "1") (pinfunction "1_1") (pintype "passive"))
      (node (ref "C10") (pin "1") (pinfunction "1_1") (pintype "passive"))
      (node (ref "C2") (pin "P") (pinfunction "P_P") (pintype "passive"))
      (node (ref "C20") (pin "P") (pinfunction "P_P") (pintype "passive"))
      (node (ref "C23") (pin "2") (pinfunction "2_2") (pintype "passive"))
      (node (ref "C24") (pin "2") (pinfunction "2_2") (pintype "passive"))
      (node (ref "C27") (pin "1") (pinfunction "1_1") (pintype "passive"))
      (node (ref "C28") (pin "1") (pinfunction "1_1") (pintype "passive"))
      (node (ref "C5") (pin "2") (pinfunction "2_2") (pintype "passive"))
      (node (ref "C6") (pin "2") (pinfunction "2_2") (pintype "passive"))
      (node (ref "C9") (pin "1") (pinfunction "1_1") (pintype "passive"))
      (node (ref "F2") (pin "2_1") (pinfunction "2_2_1") (pintype "passive"))
      (node (ref "F2") (pin "2_2") (pinfunction "2_2_2") (pintype "passive"))
      (node (ref "U3") (pin "7") (pinfunction "VS_7") (pintype "power_in"))
      (node (ref "U4") (pin "7") (pinfunction "VS_7") (pintype "power_in"))
      (node (ref "U8") (pin "7") (pinfunction "VS_7") (pintype "power_in"))
      (node (ref "U9") (pin "7") (pinfunction "VS_7") (pintype "power_in"))
    )
    (net (code "158") (name "VCC_M5M6") (class "Default")
      (node (ref "*3") (pin "1") (pinfunction "1_1") (pintype "passive"))
      (node (ref "C37") (pin "P") (pinfunction "P_P") (pintype "passive"))
      (node (ref "C39") (pin "2") (pinfunction "2_2") (pintype "passive"))
      (node (ref "C40") (pin "2") (pinfunction "2_2") (pintype "passive"))
      (node (ref "C43") (pin "1") (pinfunction "1_1") (pintype "passive"))
      (node (ref "C44") (pin "1") (pinfunction "1_1") (pintype "passive"))
      (node (ref "C55") (pin "P") (pinfunction "P_P") (pintype "passive"))
      (node (ref "C57") (pin "2") (pinfunction "2_2") (pintype "passive"))
      (node (ref "C58") (pin "2") (pinfunction "2_2") (pintype "passive"))
      (node (ref "C61") (pin "1") (pinfunction "1_1") (pintype "passive"))
      (node (ref "C62") (pin "1") (pinfunction "1_1") (pintype "passive"))
      (node (ref "F3") (pin "2_1") (pinfunction "2_2_1") (pintype "passive"))
      (node (ref "F3") (pin "2_2") (pinfunction "2_2_2") (pintype "passive"))
      (node (ref "U10") (pin "7") (pinfunction "VS_7") (pintype "power_in"))
      (node (ref "U11") (pin "7") (pinfunction "VS_7") (pintype "power_in"))
      (node (ref "U16") (pin "7") (pinfunction "VS_7") (pintype "power_in"))
      (node (ref "U17") (pin "7") (pinfunction "VS_7") (pintype "power_in"))
    )
    (net (code "159") (name "VCC_M7M8") (class "Default")
      (node (ref "*4") (pin "1") (pinfunction "1_1") (pintype "passive"))
      (node (ref "C38") (pin "P") (pinfunction "P_P") (pintype "passive"))
      (node (ref "C41") (pin "2") (pinfunction "2_2") (pintype "passive"))
      (node (ref "C42") (pin "2") (pinfunction "2_2") (pintype "passive"))
      (node (ref "C45") (pin "1") (pinfunction "1_1") (pintype "passive"))
      (node (ref "C46") (pin "1") (pinfunction "1_1") (pintype "passive"))
      (node (ref "C56") (pin "P") (pinfunction "P_P") (pintype "passive"))
      (node (ref "C59") (pin "2") (pinfunction "2_2") (pintype "passive"))
      (node (ref "C60") (pin "2") (pinfunction "2_2") (pintype "passive"))
      (node (ref "C65") (pin "1") (pinfunction "1_1") (pintype "passive"))
      (node (ref "C66") (pin "1") (pinfunction "1_1") (pintype "passive"))
      (node (ref "F4") (pin "2_1") (pinfunction "2_2_1") (pintype "passive"))
      (node (ref "F4") (pin "2_2") (pinfunction "2_2_2") (pintype "passive"))
      (node (ref "U12") (pin "7") (pinfunction "VS_7") (pintype "power_in"))
      (node (ref "U13") (pin "7") (pinfunction "VS_7") (pintype "power_in"))
      (node (ref "U18") (pin "7") (pinfunction "VS_7") (pintype "power_in"))
      (node (ref "U19") (pin "7") (pinfunction "VS_7") (pintype "power_in"))
    )
    (net (code "160") (name "unconnected-(J9-Pad2)") (class "Default")
      (node (ref "J9") (pin "2") (pinfunction "2_2") (pintype "passive+no_connect"))
    )
    (net (code "161") (name "unconnected-(J14-Pad2)") (class "Default")
      (node (ref "J14") (pin "2") (pinfunction "2_2") (pintype "passive+no_connect"))
    )
    (net (code "162") (name "unconnected-(J22-Pad1)") (class "Default")
      (node (ref "J22") (pin "1") (pinfunction "1_1") (pintype "passive+no_connect"))
    )
    (net (code "163") (name "unconnected-(J22-Pad2)") (class "Default")
      (node (ref "J22") (pin "2") (pinfunction "2_2") (pintype "passive+no_connect"))
    )
    (net (code "164") (name "unconnected-(J22-Pad3)") (class "Default")
      (node (ref "J22") (pin "3") (pinfunction "3_3") (pintype "passive+no_connect"))
    )
    (net (code "165") (name "unconnected-(J22-Pad4)") (class "Default")
      (node (ref "J22") (pin "4") (pinfunction "4_4") (pintype "passive+no_connect"))
    )
    (net (code "166") (name "unconnected-(J22-Pad7)") (class "Default")
      (node (ref "J22") (pin "7") (pinfunction "7_7") (pintype "passive+no_connect"))
    )
    (net (code "167") (name "unconnected-(J22-Pad8)") (class "Default")
      (node (ref "J22") (pin "8") (pinfunction "8_8") (pintype "passive+no_connect"))
    )
    (net (code "168") (name "unconnected-(J23-SHIELD-PadS1)") (class "Default")
      (node (ref "J23") (pin "S1") (pinfunction "SHIELD_S1") (pintype "passive+no_connect"))
    )
    (net (code "169") (name "unconnected-(J23-SHIELD-PadS2)") (class "Default")
      (node (ref "J23") (pin "S2") (pinfunction "SHIELD_S2") (pintype "passive+no_connect"))
    )
    (net (code "170") (name "unconnected-(J28-Pad7)") (class "Default")
      (node (ref "J28") (pin "7") (pinfunction "7_7") (pintype "passive+no_connect"))
    )
    (net (code "171") (name "unconnected-(J28-SHIELD-PadSH3)") (class "Default")
      (node (ref "J28") (pin "SH3") (pinfunction "SHIELD_SH3") (pintype "passive"))
    )
    (net (code "172") (name "unconnected-(J28-SHIELD-PadSH4)") (class "Default")
      (node (ref "J28") (pin "SH4") (pinfunction "SHIELD_SH4") (pintype "passive"))
    )
    (net (code "173") (name "unconnected-(S1-COM_1-Pad3)") (class "Default")
      (node (ref "S1") (pin "3") (pinfunction "COM_1_3") (pintype "input+no_connect"))
    )
    (net (code "174") (name "unconnected-(S1-NO_1-Pad1)") (class "Default")
      (node (ref "S1") (pin "1") (pinfunction "NO_1_1") (pintype "bidirectional+no_connect"))
    )
    (net (code "175") (name "unconnected-(S2-COM_1-Pad3)") (class "Default")
      (node (ref "S2") (pin "3") (pinfunction "COM_1_3") (pintype "input+no_connect"))
    )
    (net (code "176") (name "unconnected-(S2-NO_1-Pad1)") (class "Default")
      (node (ref "S2") (pin "1") (pinfunction "NO_1_1") (pintype "bidirectional+no_connect"))
    )
    (net (code "177") (name "unconnected-(S3-COM_1-Pad3)") (class "Default")
      (node (ref "S3") (pin "3") (pinfunction "COM_1_3") (pintype "input+no_connect"))
    )
    (net (code "178") (name "unconnected-(S3-NO_1-Pad1)") (class "Default")
      (node (ref "S3") (pin "1") (pinfunction "NO_1_1") (pintype "bidirectional+no_connect"))
    )
    (net (code "179") (name "unconnected-(S4-COM_1-Pad3)") (class "Default")
      (node (ref "S4") (pin "3") (pinfunction "COM_1_3") (pintype "input+no_connect"))
    )
    (net (code "180") (name "unconnected-(S4-NO_1-Pad1)") (class "Default")
      (node (ref "S4") (pin "1") (pinfunction "NO_1_1") (pintype "bidirectional+no_connect"))
    )
    (net (code "181") (name "unconnected-(S5-COM_1-Pad3)") (class "Default")
      (node (ref "S5") (pin "3") (pinfunction "COM_1_3") (pintype "input+no_connect"))
    )
    (net (code "182") (name "unconnected-(S5-NO_1-Pad1)") (class "Default")
      (node (ref "S5") (pin "1") (pinfunction "NO_1_1") (pintype "bidirectional+no_connect"))
    )
    (net (code "183") (name "unconnected-(S6-COM_1-Pad3)") (class "Default")
      (node (ref "S6") (pin "3") (pinfunction "COM_1_3") (pintype "input+no_connect"))
    )
    (net (code "184") (name "unconnected-(S6-NO_1-Pad1)") (class "Default")
      (node (ref "S6") (pin "1") (pinfunction "NO_1_1") (pintype "bidirectional+no_connect"))
    )
    (net (code "185") (name "unconnected-(S7-COM_1-Pad3)") (class "Default")
      (node (ref "S7") (pin "3") (pinfunction "COM_1_3") (pintype "input+no_connect"))
    )
    (net (code "186") (name "unconnected-(S7-NO_1-Pad1)") (class "Default")
      (node (ref "S7") (pin "1") (pinfunction "NO_1_1") (pintype "bidirectional+no_connect"))
    )
    (net (code "187") (name "unconnected-(S8-COM_1-Pad3)") (class "Default")
      (node (ref "S8") (pin "3") (pinfunction "COM_1_3") (pintype "input+no_connect"))
    )
    (net (code "188") (name "unconnected-(S8-NO_1-Pad1)") (class "Default")
      (node (ref "S8") (pin "1") (pinfunction "NO_1_1") (pintype "bidirectional+no_connect"))
    )
    (net (code "189") (name "unconnected-(S9-COM_1-Pad3)") (class "Default")
      (node (ref "S9") (pin "3") (pinfunction "COM_1_3") (pintype "input+no_connect"))
    )
    (net (code "190") (name "unconnected-(S9-NO_1-Pad1)") (class "Default")
      (node (ref "S9") (pin "1") (pinfunction "NO_1_1") (pintype "bidirectional+no_connect"))
    )
    (net (code "191") (name "unconnected-(S10-COM_1-Pad3)") (class "Default")
      (node (ref "S10") (pin "3") (pinfunction "COM_1_3") (pintype "input+no_connect"))
    )
    (net (code "192") (name "unconnected-(S10-NO_1-Pad1)") (class "Default")
      (node (ref "S10") (pin "1") (pinfunction "NO_1_1") (pintype "bidirectional+no_connect"))
    )
    (net (code "193") (name "unconnected-(S11-COM_1-Pad3)") (class "Default")
      (node (ref "S11") (pin "3") (pinfunction "COM_1_3") (pintype "input+no_connect"))
    )
    (net (code "194") (name "unconnected-(S11-NO_1-Pad1)") (class "Default")
      (node (ref "S11") (pin "1") (pinfunction "NO_1_1") (pintype "bidirectional+no_connect"))
    )
    (net (code "195") (name "unconnected-(S12-COM_1-Pad3)") (class "Default")
      (node (ref "S12") (pin "3") (pinfunction "COM_1_3") (pintype "input+no_connect"))
    )
    (net (code "196") (name "unconnected-(S12-NO_1-Pad1)") (class "Default")
      (node (ref "S12") (pin "1") (pinfunction "NO_1_1") (pintype "bidirectional+no_connect"))
    )
    (net (code "197") (name "unconnected-(S13-COM_1-Pad3)") (class "Default")
      (node (ref "S13") (pin "3") (pinfunction "COM_1_3") (pintype "input+no_connect"))
    )
    (net (code "198") (name "unconnected-(S13-NO_1-Pad1)") (class "Default")
      (node (ref "S13") (pin "1") (pinfunction "NO_1_1") (pintype "bidirectional+no_connect"))
    )
    (net (code "199") (name "unconnected-(S14-COM_1-Pad3)") (class "Default")
      (node (ref "S14") (pin "3") (pinfunction "COM_1_3") (pintype "input+no_connect"))
    )
    (net (code "200") (name "unconnected-(S14-NO_1-Pad1)") (class "Default")
      (node (ref "S14") (pin "1") (pinfunction "NO_1_1") (pintype "bidirectional+no_connect"))
    )
    (net (code "201") (name "unconnected-(S15-COM_1-Pad3)") (class "Default")
      (node (ref "S15") (pin "3") (pinfunction "COM_1_3") (pintype "input+no_connect"))
    )
    (net (code "202") (name "unconnected-(S15-NO_1-Pad1)") (class "Default")
      (node (ref "S15") (pin "1") (pinfunction "NO_1_1") (pintype "bidirectional+no_connect"))
    )
    (net (code "203") (name "unconnected-(S16-COM_1-Pad3)") (class "Default")
      (node (ref "S16") (pin "3") (pinfunction "COM_1_3") (pintype "input+no_connect"))
    )
    (net (code "204") (name "unconnected-(S16-NO_1-Pad1)") (class "Default")
      (node (ref "S16") (pin "1") (pinfunction "NO_1_1") (pintype "bidirectional+no_connect"))
    )
    (net (code "205") (name "unconnected-(SW1-NO-Pad3)") (class "Default")
      (node (ref "SW1") (pin "3") (pinfunction "NO_3") (pintype "passive+no_connect"))
    )
    (net (code "206") (name "unconnected-(U1-IS-Pad6)") (class "Default")
      (node (ref "U1") (pin "6") (pinfunction "IS_6") (pintype "output+no_connect"))
    )
    (net (code "207") (name "unconnected-(U2-IS-Pad6)") (class "Default")
      (node (ref "U2") (pin "6") (pinfunction "IS_6") (pintype "output+no_connect"))
    )
    (net (code "208") (name "unconnected-(U3-IS-Pad6)") (class "Default")
      (node (ref "U3") (pin "6") (pinfunction "IS_6") (pintype "output+no_connect"))
    )
    (net (code "209") (name "unconnected-(U4-IS-Pad6)") (class "Default")
      (node (ref "U4") (pin "6") (pinfunction "IS_6") (pintype "output+no_connect"))
    )
    (net (code "210") (name "unconnected-(U5-0E_1-Pad53)") (class "Default")
      (node (ref "U5") (pin "53") (pinfunction "0E_1_53") (pintype "passive+no_connect"))
    )
    (net (code "211") (name "unconnected-(U5-0E_2-Pad59)") (class "Default")
      (node (ref "U5") (pin "59") (pinfunction "0E_2_59") (pintype "passive+no_connect"))
    )
    (net (code "212") (name "unconnected-(U5-GND_2-Pad60)") (class "Default")
      (node (ref "U5") (pin "60") (pinfunction "GND_2_60") (pintype "passive+no_connect"))
    )
    (net (code "213") (name "unconnected-(U5-SCL_2-Pad58)") (class "Default")
      (node (ref "U5") (pin "58") (pinfunction "SCL_2_58") (pintype "passive+no_connect"))
    )
    (net (code "214") (name "unconnected-(U5-SDA_2-Pad57)") (class "Default")
      (node (ref "U5") (pin "57") (pinfunction "SDA_2_57") (pintype "passive+no_connect"))
    )
    (net (code "215") (name "unconnected-(U5-V+_1-Pad49)") (class "Default")
      (node (ref "U5") (pin "49") (pinfunction "V+_1_49") (pintype "passive+no_connect"))
    )
    (net (code "216") (name "unconnected-(U5-V+_2-Pad55)") (class "Default")
      (node (ref "U5") (pin "55") (pinfunction "V+_2_55") (pintype "passive+no_connect"))
    )
    (net (code "217") (name "unconnected-(U5-VCC_2-Pad56)") (class "Default")
      (node (ref "U5") (pin "56") (pinfunction "VCC_2_56") (pintype "passive+no_connect"))
    )
    (net (code "218") (name "unconnected-(U6-IS-Pad6)") (class "Default")
      (node (ref "U6") (pin "6") (pinfunction "IS_6") (pintype "output+no_connect"))
    )
    (net (code "219") (name "unconnected-(U7-IS-Pad6)") (class "Default")
      (node (ref "U7") (pin "6") (pinfunction "IS_6") (pintype "output+no_connect"))
    )
    (net (code "220") (name "unconnected-(U8-IS-Pad6)") (class "Default")
      (node (ref "U8") (pin "6") (pinfunction "IS_6") (pintype "output+no_connect"))
    )
    (net (code "221") (name "unconnected-(U9-IS-Pad6)") (class "Default")
      (node (ref "U9") (pin "6") (pinfunction "IS_6") (pintype "output+no_connect"))
    )
    (net (code "222") (name "unconnected-(U10-IS-Pad6)") (class "Default")
      (node (ref "U10") (pin "6") (pinfunction "IS_6") (pintype "output+no_connect"))
    )
    (net (code "223") (name "unconnected-(U11-IS-Pad6)") (class "Default")
      (node (ref "U11") (pin "6") (pinfunction "IS_6") (pintype "output+no_connect"))
    )
    (net (code "224") (name "unconnected-(U12-IS-Pad6)") (class "Default")
      (node (ref "U12") (pin "6") (pinfunction "IS_6") (pintype "output+no_connect"))
    )
    (net (code "225") (name "unconnected-(U13-IS-Pad6)") (class "Default")
      (node (ref "U13") (pin "6") (pinfunction "IS_6") (pintype "output+no_connect"))
    )
    (net (code "226") (name "unconnected-(U14-3.3V-Pad3.3V_1)") (class "Default")
      (node (ref "U14") (pin "3.3V_1") (pinfunction "3.3V_3.3V_1") (pintype "power_in+no_connect"))
    )
    (net (code "227") (name "unconnected-(U14-3.3V-Pad3.3V_2)") (class "Default")
      (node (ref "U14") (pin "3.3V_2") (pinfunction "3.3V_3.3V_2") (pintype "power_in+no_connect"))
    )
    (net (code "228") (name "unconnected-(U14-3.3V-Pad3.3V_3)") (class "Default")
      (node (ref "U14") (pin "3.3V_3") (pinfunction "3.3V_3.3V_3") (pintype "power_in+no_connect"))
    )
    (net (code "229") (name "unconnected-(U14-GND-PadGND4)") (class "Default")
      (node (ref "U14") (pin "GND4") (pinfunction "GND_GND4") (pintype "power_in+no_connect"))
    )
    (net (code "230") (name "unconnected-(U14-GND-PadGND5)") (class "Default")
      (node (ref "U14") (pin "GND5") (pinfunction "GND_GND5") (pintype "power_in+no_connect"))
    )
    (net (code "231") (name "unconnected-(U14-PadLED)") (class "Default")
      (node (ref "U14") (pin "LED") (pinfunction "LED_LED") (pintype "bidirectional+no_connect"))
    )
    (net (code "232") (name "unconnected-(U14-PadON{slash}OFF)") (class "Default")
      (node (ref "U14") (pin "ON/OFF") (pinfunction "ON/OFF_ON/OFF") (pintype "bidirectional"))
    )
    (net (code "233") (name "unconnected-(U14-PadPROGRAM)") (class "Default")
      (node (ref "U14") (pin "PROGRAM") (pinfunction "PROGRAM_PROGRAM") (pintype "bidirectional"))
    )
    (net (code "234") (name "unconnected-(U14-PadR+)") (class "Default")
      (node (ref "U14") (pin "R+") (pinfunction "R+_R+") (pintype "bidirectional+no_connect"))
    )
    (net (code "235") (name "unconnected-(U14-PadR-)") (class "Default")
      (node (ref "U14") (pin "R-") (pinfunction "R-_R-") (pintype "bidirectional+no_connect"))
    )
    (net (code "236") (name "unconnected-(U14-PadT+)") (class "Default")
      (node (ref "U14") (pin "T+") (pinfunction "T+_T+") (pintype "bidirectional+no_connect"))
    )
    (net (code "237") (name "unconnected-(U14-PadT-)") (class "Default")
      (node (ref "U14") (pin "T-") (pinfunction "T-_T-") (pintype "bidirectional+no_connect"))
    )
    (net (code "238") (name "unconnected-(U14-PadVBAT)") (class "Default")
      (node (ref "U14") (pin "VBAT") (pinfunction "VBAT_VBAT") (pintype "passive+no_connect"))
    )
    (net (code "239") (name "unconnected-(U14-PadVUSB)") (class "Default")
      (node (ref "U14") (pin "VUSB") (pinfunction "VUSB_VUSB") (pintype "passive+no_connect"))
    )
    (net (code "240") (name "unconnected-(U15-3VO-Pad2)") (class "Default")
      (node (ref "U15") (pin "2") (pinfunction "3VO_2") (pintype "power_in+no_connect"))
    )
    (net (code "241") (name "unconnected-(U15-ADR-Pad9)") (class "Default")
      (node (ref "U15") (pin "9") (pinfunction "ADR_9") (pintype "passive+no_connect"))
    )
    (net (code "242") (name "unconnected-(U15-INT-Pad10)") (class "Default")
      (node (ref "U15") (pin "10") (pinfunction "INT_10") (pintype "output+no_connect"))
    )
    (net (code "243") (name "unconnected-(U15-PS0-Pad8)") (class "Default")
      (node (ref "U15") (pin "8") (pinfunction "PS0_8") (pintype "bidirectional+no_connect"))
    )
    (net (code "244") (name "unconnected-(U15-PS1-Pad7)") (class "Default")
      (node (ref "U15") (pin "7") (pinfunction "PS1_7") (pintype "bidirectional+no_connect"))
    )
    (net (code "245") (name "unconnected-(U15-RST-Pad6)") (class "Default")
      (node (ref "U15") (pin "6") (pinfunction "RST_6") (pintype "input+no_connect"))
    )
    (net (code "246") (name "unconnected-(U16-IS-Pad6)") (class "Default")
      (node (ref "U16") (pin "6") (pinfunction "IS_6") (pintype "output+no_connect"))
    )
    (net (code "247") (name "unconnected-(U17-IS-Pad6)") (class "Default")
      (node (ref "U17") (pin "6") (pinfunction "IS_6") (pintype "output+no_connect"))
    )
    (net (code "248") (name "unconnected-(U18-IS-Pad6)") (class "Default")
      (node (ref "U18") (pin "6") (pinfunction "IS_6") (pintype "output+no_connect"))
    )
    (net (code "249") (name "unconnected-(U19-IS-Pad6)") (class "Default")
      (node (ref "U19") (pin "6") (pinfunction "IS_6") (pintype "output+no_connect"))
    )
    (net (code "250") (name "unconnected-(sw2-C2-Pad4)") (class "Default")
      (node (ref "sw2") (pin "4") (pinfunction "C2_4") (pintype "passive"))
    )
  )
)
